# elasticNode.net
KiCad netlist of a schematic drawn in EAGLE
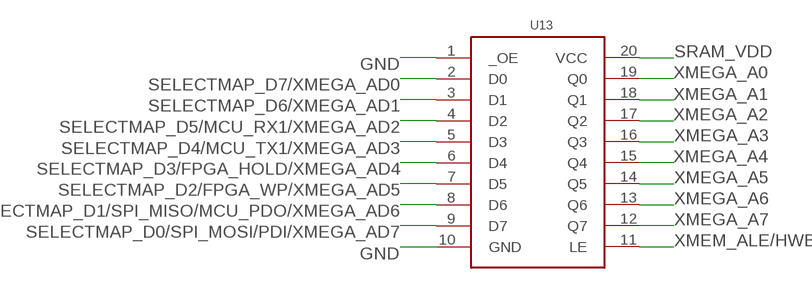
[diagram p0: schematic, sheet 1, part 1 of 2]
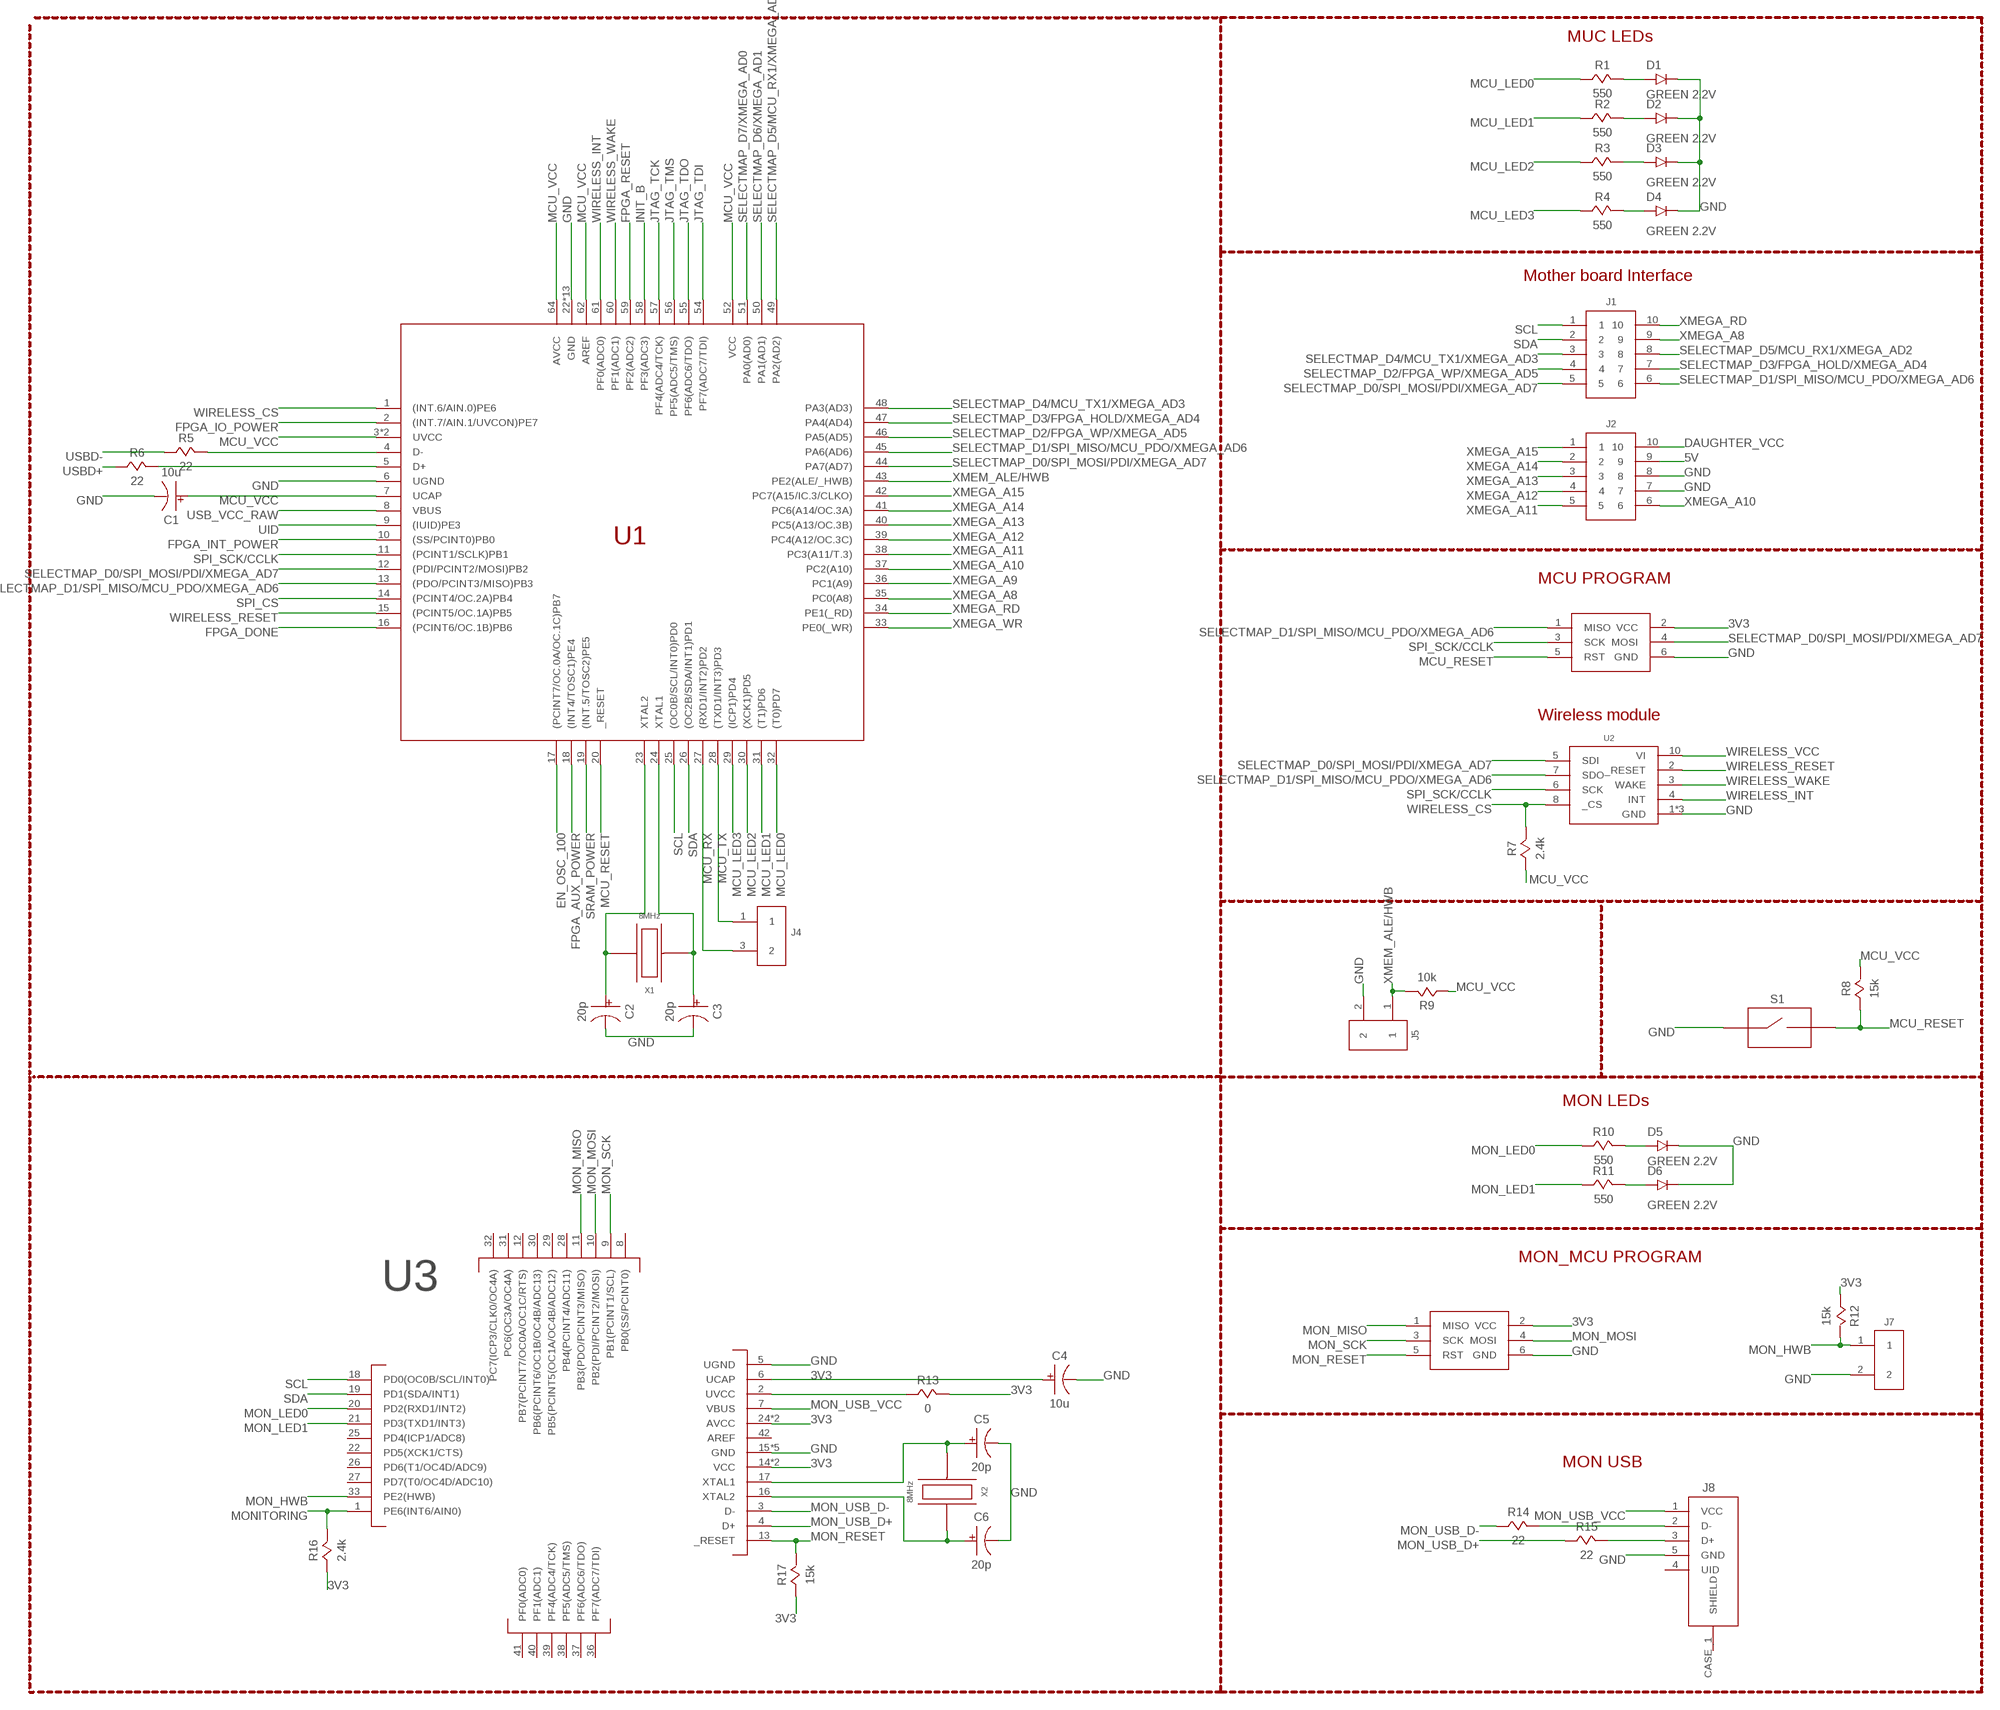
[diagram p1: schematic, sheet 1, part 2 of 2]
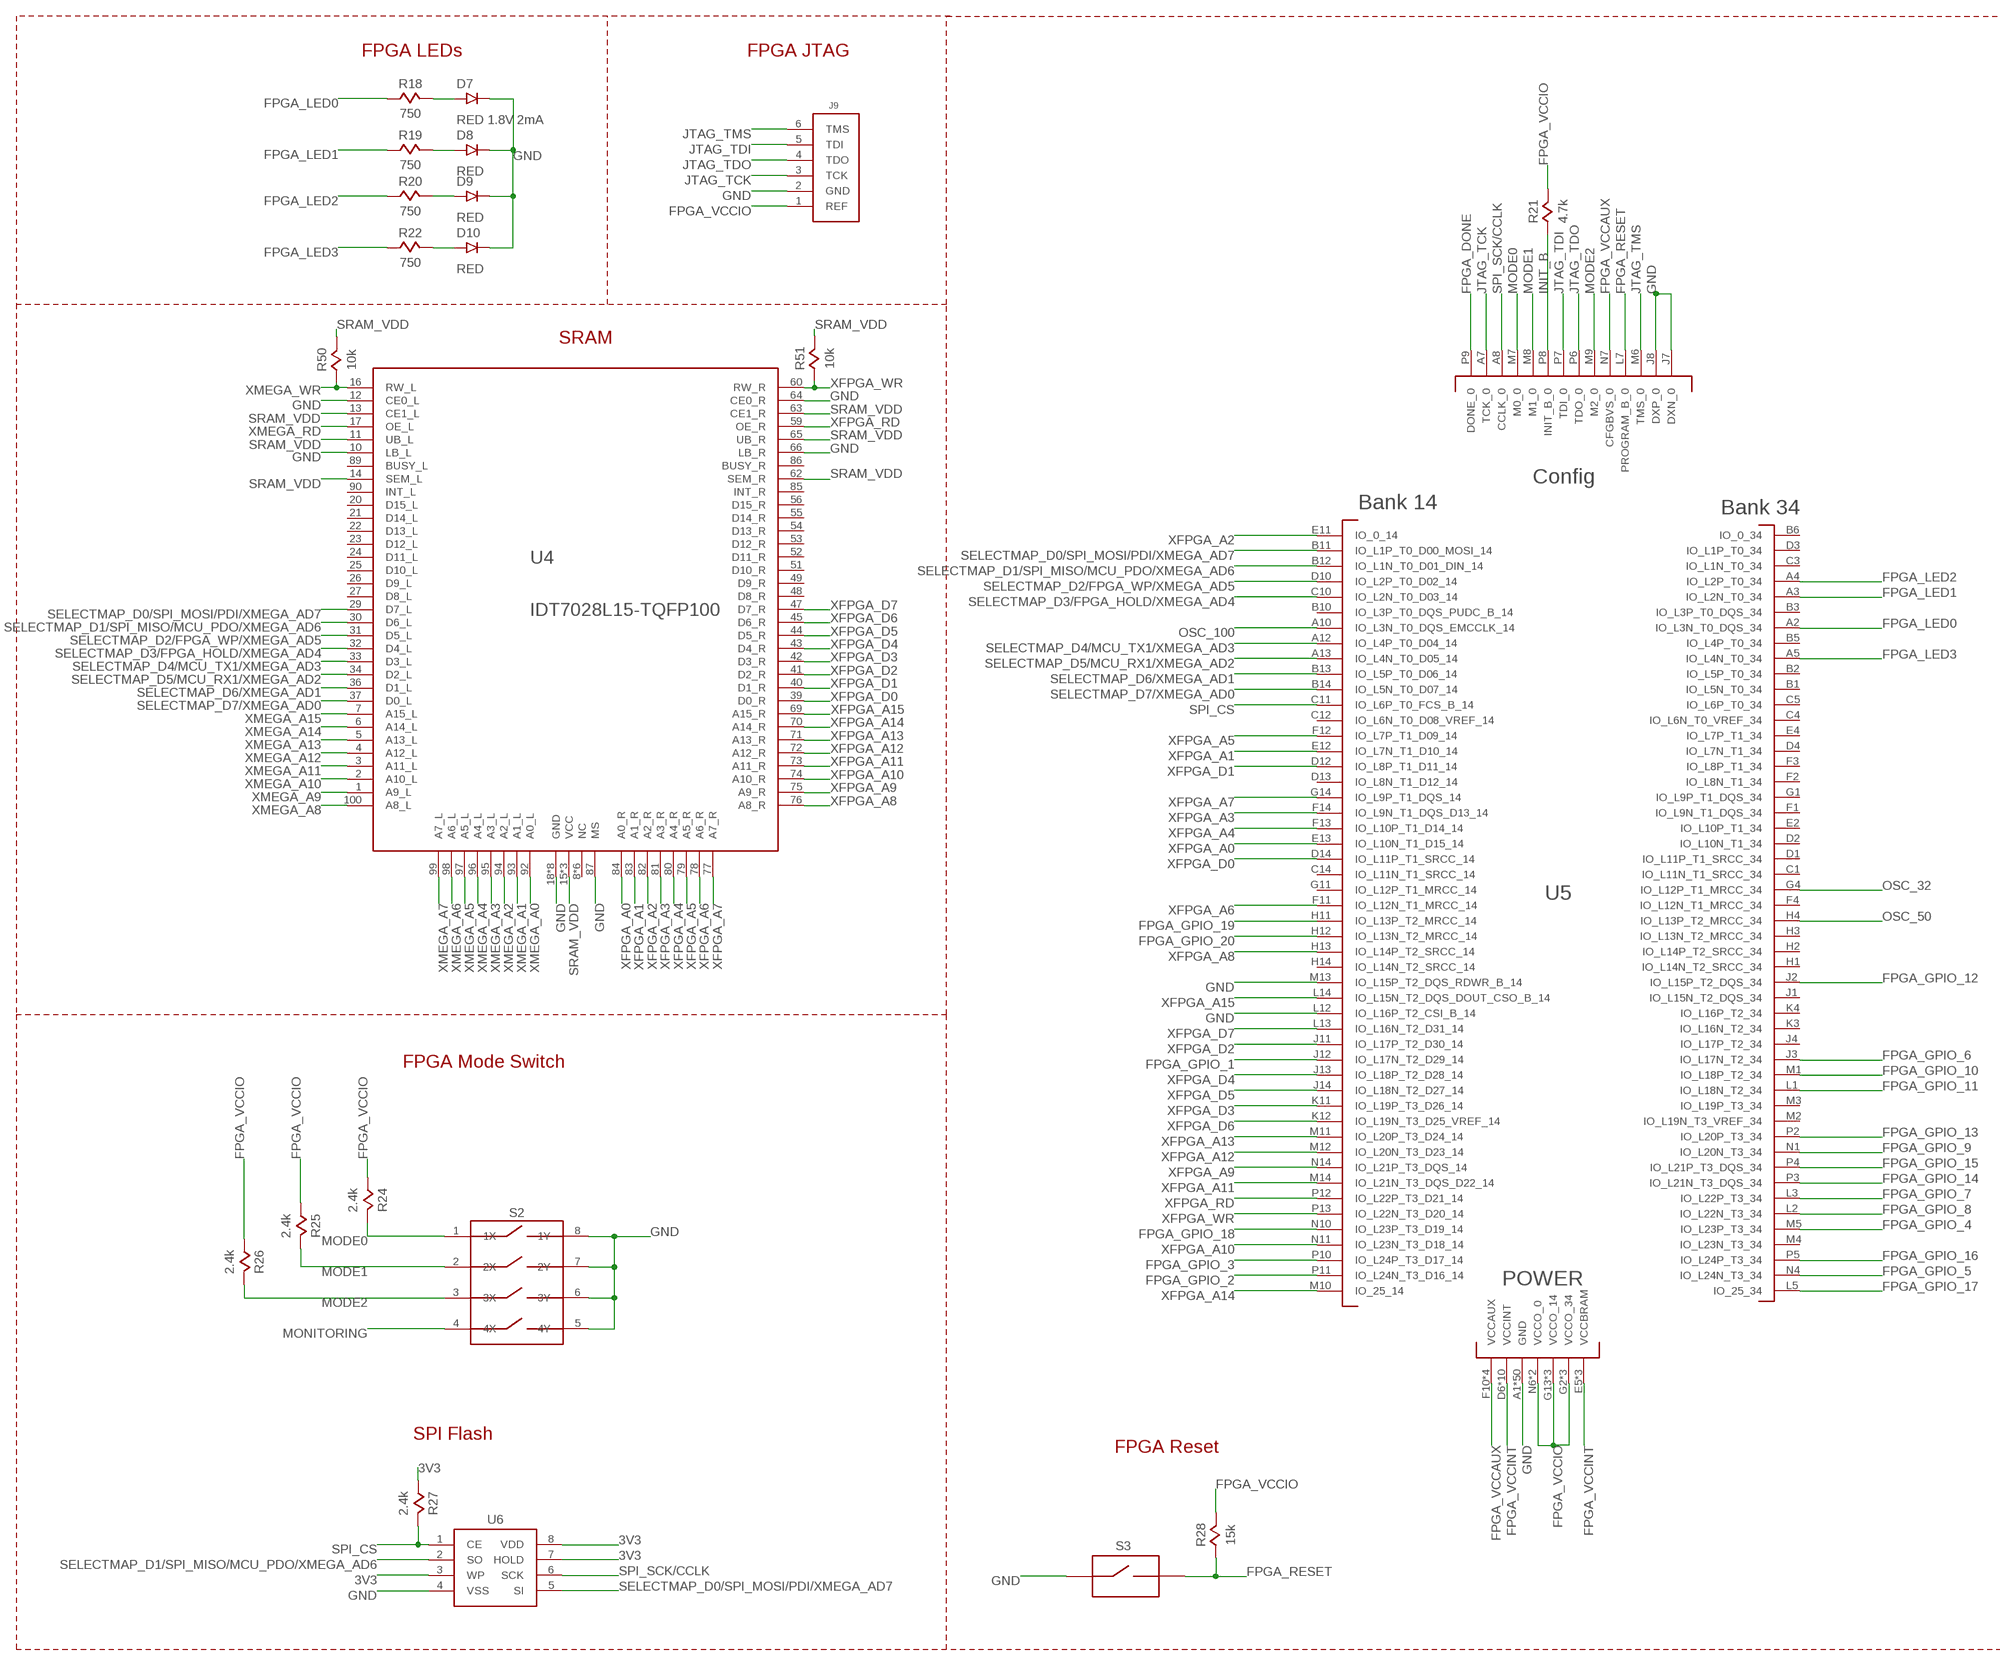
[diagram p2: schematic, sheet 2, part 1 of 2]
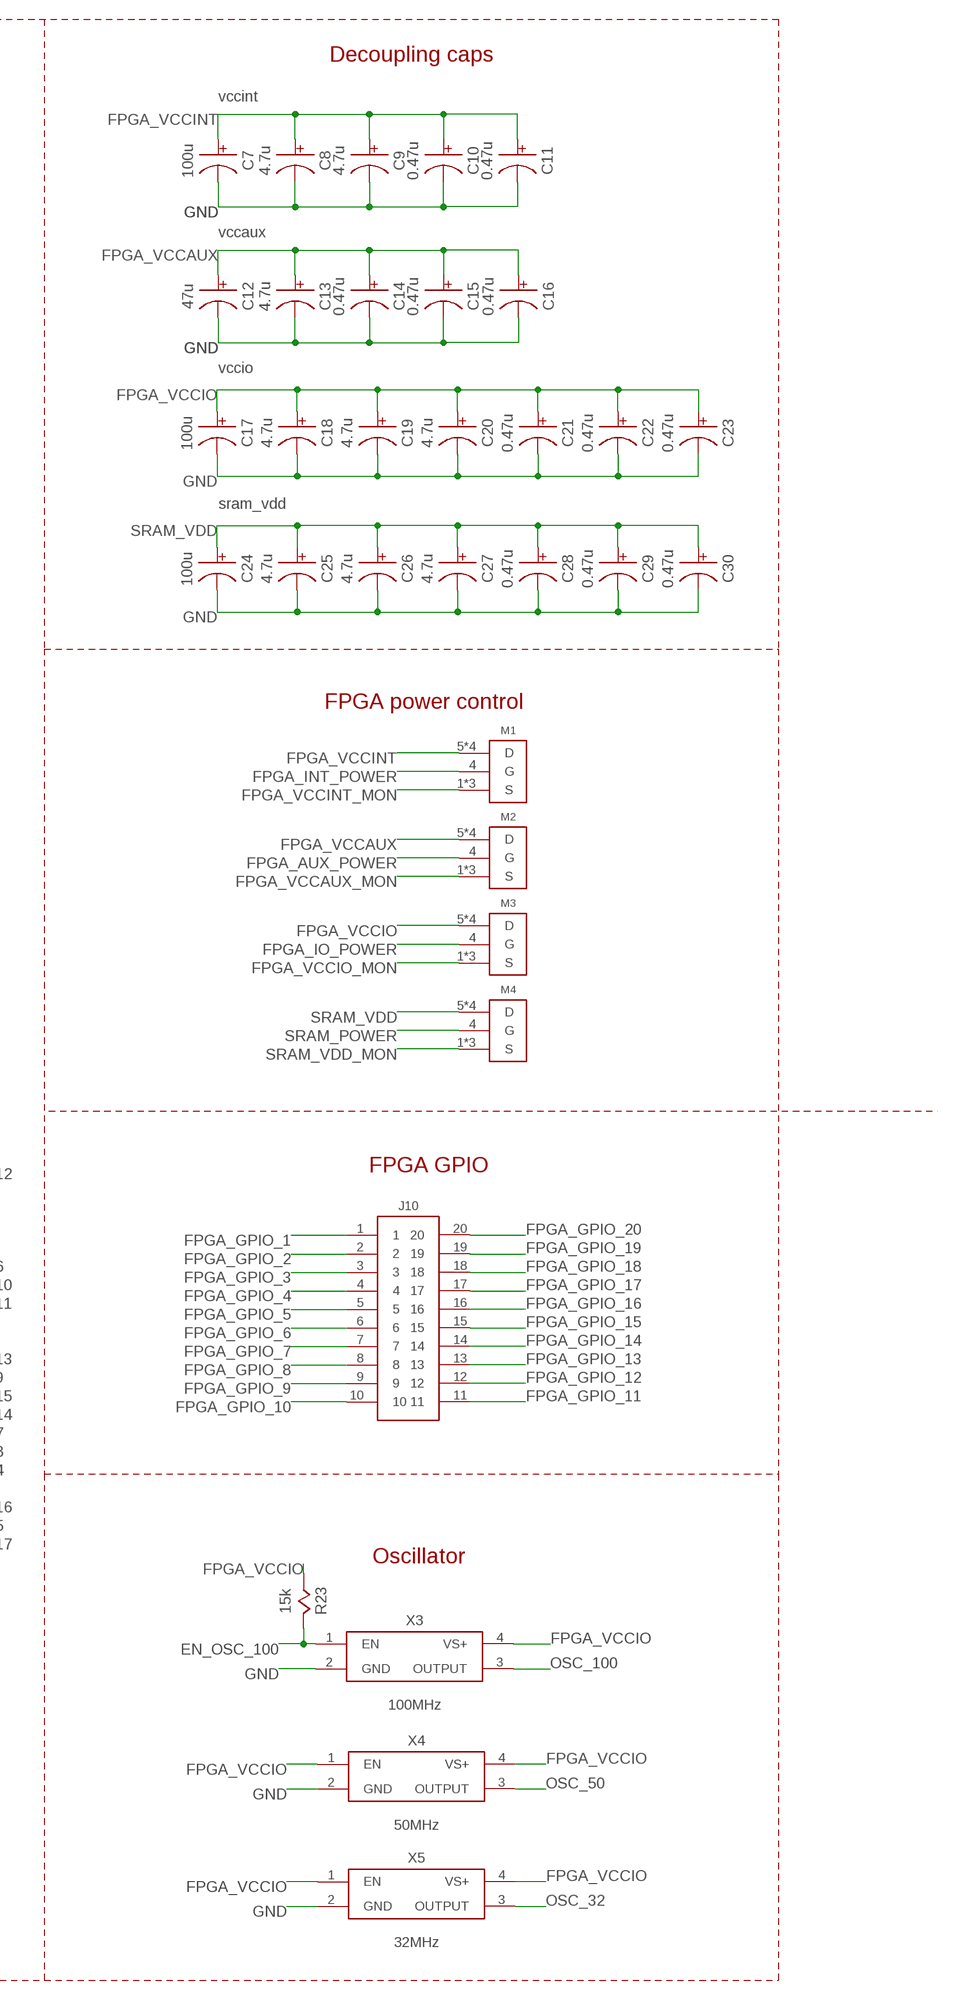
[diagram p3: schematic, sheet 2, part 2 of 2]
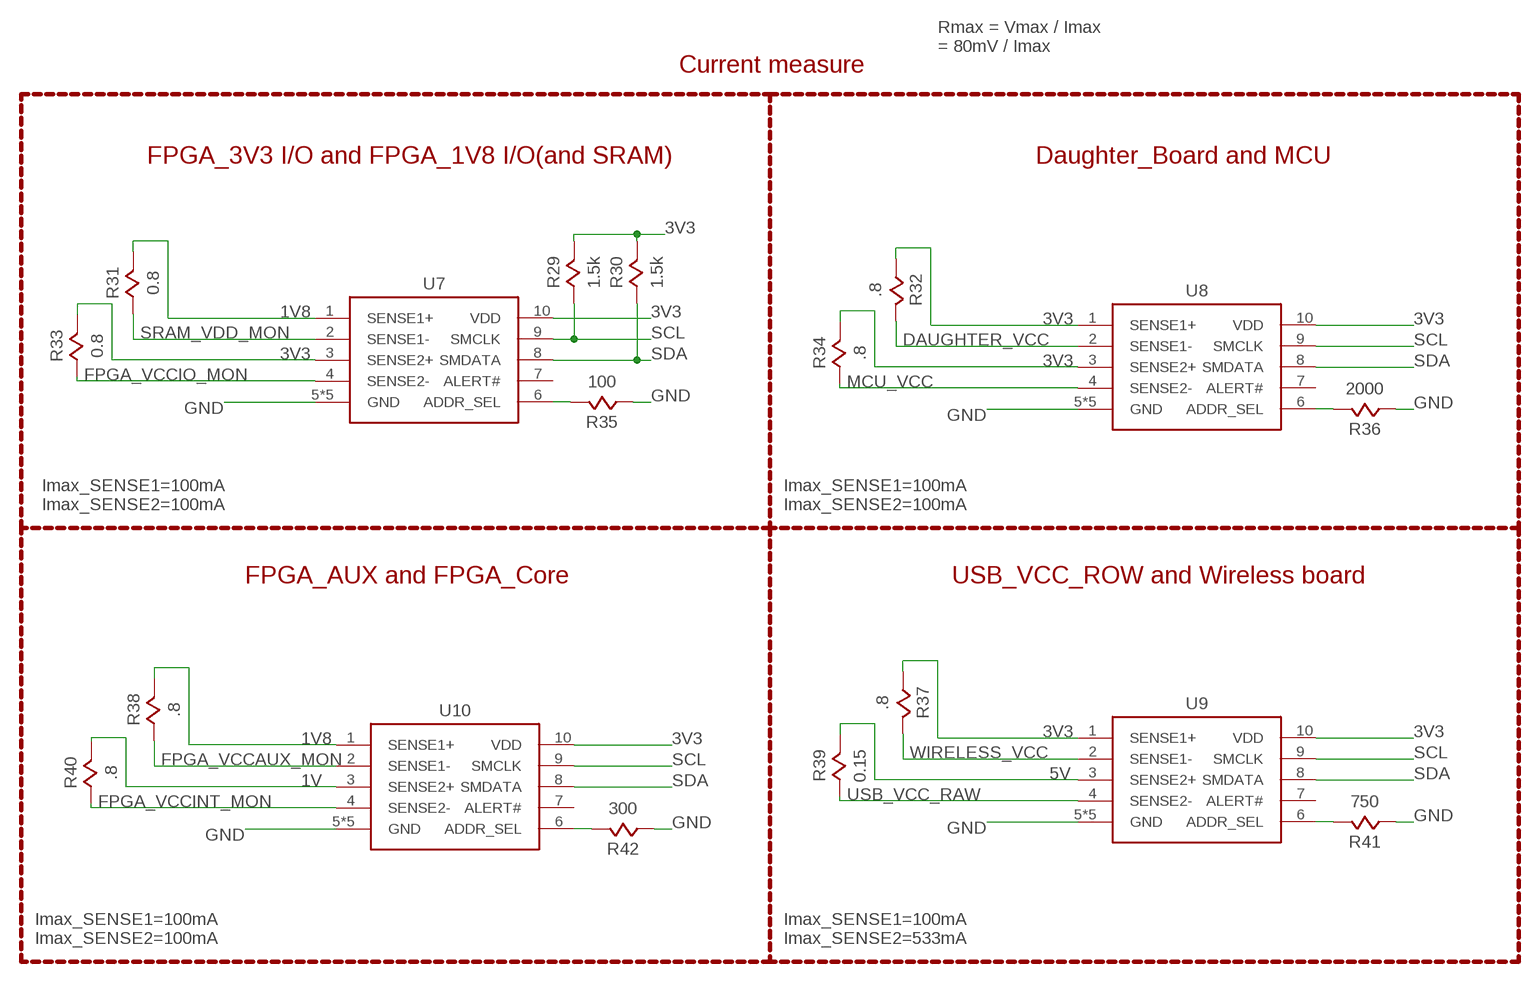
[diagram p4: schematic, sheet 3]
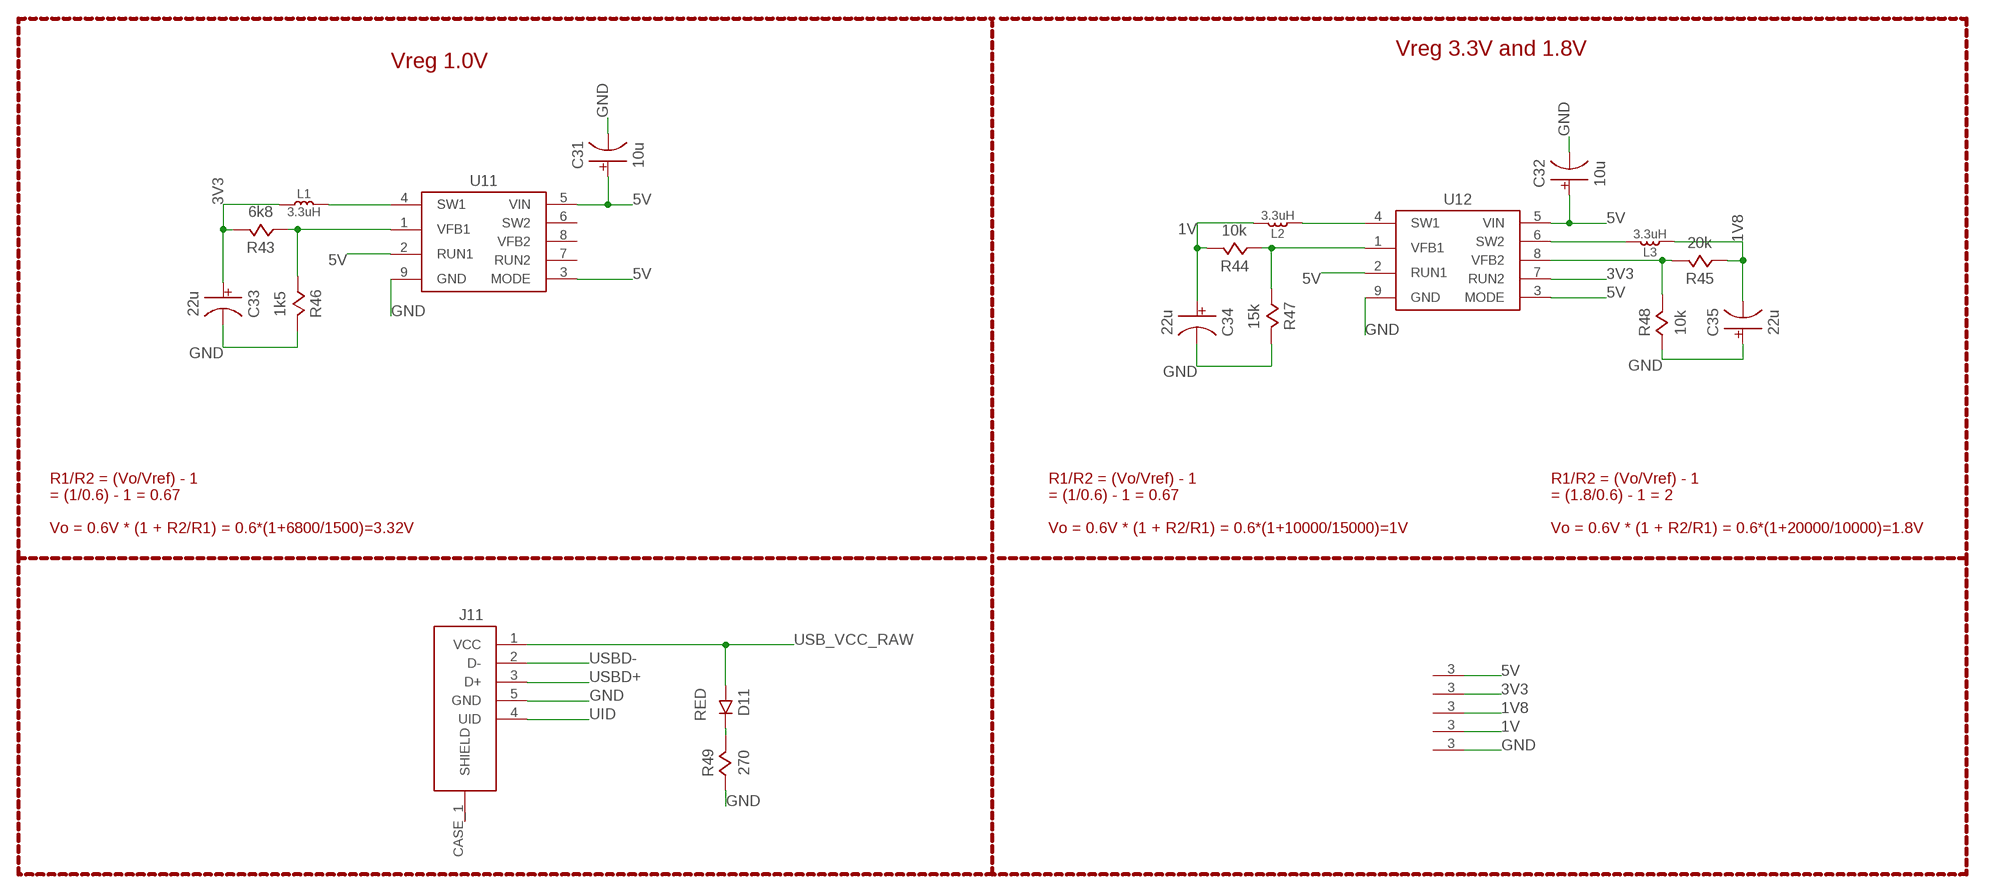
[diagram p5: schematic, sheet 4]

(export (version "E")
  (design (tool "Eeschema 10.0.6"))
  (components
    (comp (ref "C31")
      (value "10u")
      (footprint "eagle-import:0805")
      (libsource (lib "eagle-import") (part "CAPACITOR0805"))
    )
    (comp (ref "C32")
      (value "10u")
      (footprint "eagle-import:0805")
      (libsource (lib "eagle-import") (part "CAPACITOR0805"))
    )
    (comp (ref "C33")
      (value "22u")
      (footprint "eagle-import:0805")
      (libsource (lib "eagle-import") (part "CAPACITOR0805"))
    )
    (comp (ref "C34")
      (value "22u")
      (footprint "eagle-import:0805")
      (libsource (lib "eagle-import") (part "CAPACITOR0805"))
    )
    (comp (ref "C35")
      (value "22u")
      (footprint "eagle-import:0805")
      (libsource (lib "eagle-import") (part "CAPACITOR0805"))
    )
    (comp (ref "D11")
      (value "RED")
      (footprint "eagle-import:0805")
      (libsource (lib "eagle-import") (part "LED"))
    )
    (comp (ref "J11")
      (value "USB_CONNMICRO_SMT")
      (footprint "eagle-import:USB_MICRO_B_SMT")
      (libsource (lib "eagle-import") (part "USB_CONNMICRO_SMT"))
    )
    (comp (ref "L1")
      (value "3.3uH")
      (footprint "eagle-import:0805")
      (libsource (lib "eagle-import") (part "INDUCTOR"))
    )
    (comp (ref "L2")
      (value "3.3uH")
      (footprint "eagle-import:0805")
      (libsource (lib "eagle-import") (part "INDUCTOR"))
    )
    (comp (ref "L3")
      (value "3.3uH")
      (footprint "eagle-import:0805")
      (libsource (lib "eagle-import") (part "INDUCTOR"))
    )
    (comp (ref "R43")
      (value "6k8")
      (footprint "eagle-import:0805")
      (libsource (lib "eagle-import") (part "RESISTOR"))
    )
    (comp (ref "R44")
      (value "10k")
      (footprint "eagle-import:0805")
      (libsource (lib "eagle-import") (part "RESISTOR"))
    )
    (comp (ref "R45")
      (value "20k")
      (footprint "eagle-import:0805")
      (libsource (lib "eagle-import") (part "RESISTOR"))
    )
    (comp (ref "R46")
      (value "1k5")
      (footprint "eagle-import:0805")
      (libsource (lib "eagle-import") (part "RESISTOR"))
    )
    (comp (ref "R47")
      (value "15k")
      (footprint "eagle-import:0805")
      (libsource (lib "eagle-import") (part "RESISTOR"))
    )
    (comp (ref "R48")
      (value "10k")
      (footprint "eagle-import:0805")
      (libsource (lib "eagle-import") (part "RESISTOR"))
    )
    (comp (ref "R49")
      (value "270")
      (footprint "eagle-import:0805")
      (libsource (lib "eagle-import") (part "RESISTOR"))
    )
    (comp (ref "TP1")
      (value "TEST_POINTTHT")
      (footprint "eagle-import:THT")
      (libsource (lib "eagle-import") (part "TEST_POINTTHT"))
    )
    (comp (ref "TP2")
      (value "TEST_POINTTHT")
      (footprint "eagle-import:THT")
      (libsource (lib "eagle-import") (part "TEST_POINTTHT"))
    )
    (comp (ref "TP3")
      (value "TEST_POINTTHT")
      (footprint "eagle-import:THT")
      (libsource (lib "eagle-import") (part "TEST_POINTTHT"))
    )
    (comp (ref "TP4")
      (value "TEST_POINTTHT")
      (footprint "eagle-import:THT")
      (libsource (lib "eagle-import") (part "TEST_POINTTHT"))
    )
    (comp (ref "TP5")
      (value "TEST_POINTTHT")
      (footprint "eagle-import:THT")
      (libsource (lib "eagle-import") (part "TEST_POINTTHT"))
    )
    (comp (ref "U11")
      (value "LTC3419DFN")
      (footprint "eagle-import:DFN8")
      (libsource (lib "eagle-import") (part "LTC3419DFN"))
    )
    (comp (ref "U12")
      (value "LTC3419DFN")
      (footprint "eagle-import:DFN8")
      (libsource (lib "eagle-import") (part "LTC3419DFN"))
    )
    (comp (ref "C1")
      (value "10u")
      (footprint "eagle-import:0805")
      (libsource (lib "eagle-import") (part "CAPACITOR0805"))
    )
    (comp (ref "C2")
      (value "20p")
      (footprint "eagle-import:0805")
      (libsource (lib "eagle-import") (part "CAPACITOR0805"))
    )
    (comp (ref "C3")
      (value "20p")
      (footprint "eagle-import:0805")
      (libsource (lib "eagle-import") (part "CAPACITOR0805"))
    )
    (comp (ref "C4")
      (value "10u")
      (footprint "eagle-import:0805")
      (libsource (lib "eagle-import") (part "CAPACITOR0805"))
    )
    (comp (ref "C5")
      (value "20p")
      (footprint "eagle-import:0805")
      (libsource (lib "eagle-import") (part "CAPACITOR0805"))
    )
    (comp (ref "C6")
      (value "20p")
      (footprint "eagle-import:0805")
      (libsource (lib "eagle-import") (part "CAPACITOR0805"))
    )
    (comp (ref "D1")
      (value "GREEN 2.2V")
      (footprint "eagle-import:0805")
      (libsource (lib "eagle-import") (part "LED"))
    )
    (comp (ref "D2")
      (value "GREEN 2.2V")
      (footprint "eagle-import:0805")
      (libsource (lib "eagle-import") (part "LED"))
    )
    (comp (ref "D3")
      (value "GREEN 2.2V")
      (footprint "eagle-import:0805")
      (libsource (lib "eagle-import") (part "LED"))
    )
    (comp (ref "D4")
      (value "GREEN 2.2V")
      (footprint "eagle-import:0805")
      (libsource (lib "eagle-import") (part "LED"))
    )
    (comp (ref "D5")
      (value "GREEN 2.2V")
      (footprint "eagle-import:0805")
      (libsource (lib "eagle-import") (part "LED"))
    )
    (comp (ref "D6")
      (value "GREEN 2.2V")
      (footprint "eagle-import:0805")
      (libsource (lib "eagle-import") (part "LED"))
    )
    (comp (ref "J1")
      (value "FEMALE_HEADER_5X2")
      (footprint "eagle-import:5X2_HEADER_SMT_1.27")
      (libsource (lib "eagle-import") (part "FEMALE_HEADER_5X2"))
    )
    (comp (ref "J2")
      (value "FEMALE_HEADER_5X2")
      (footprint "eagle-import:5X2_HEADER_SMT_1.27")
      (libsource (lib "eagle-import") (part "FEMALE_HEADER_5X2"))
    )
    (comp (ref "J3")
      (value "ISP_CONN_6PIN")
      (footprint "eagle-import:ICSP_SMT")
      (fields (field (name "SPICEPREFIX") "X"))
      (libsource (lib "eagle-import") (part "ISP_CONN_6PIN"))
    )
    (comp (ref "J4")
      (value "FEMALE_HEADER_2X1")
      (footprint "eagle-import:2X1_HEADER")
      (libsource (lib "eagle-import") (part "FEMALE_HEADER_2X1"))
    )
    (comp (ref "J5")
      (value "JUMPER")
      (footprint "eagle-import:JUMPER_SMT")
      (libsource (lib "eagle-import") (part "JUMPER"))
    )
    (comp (ref "J6")
      (value "ISP_CONN_6PIN")
      (footprint "eagle-import:ICSP_SMT")
      (libsource (lib "eagle-import") (part "ISP_CONN_6PIN"))
    )
    (comp (ref "J7")
      (value "JUMPER")
      (footprint "eagle-import:JUMPER_SMT")
      (libsource (lib "eagle-import") (part "JUMPER"))
    )
    (comp (ref "J8")
      (value "USB_CONNMICRO_SMT")
      (footprint "eagle-import:USB_MICRO_B_SMT")
      (libsource (lib "eagle-import") (part "USB_CONNMICRO_SMT"))
    )
    (comp (ref "R1")
      (value "550")
      (footprint "eagle-import:0805")
      (libsource (lib "eagle-import") (part "RESISTOR"))
    )
    (comp (ref "R2")
      (value "550")
      (footprint "eagle-import:0805")
      (libsource (lib "eagle-import") (part "RESISTOR"))
    )
    (comp (ref "R3")
      (value "550")
      (footprint "eagle-import:0805")
      (libsource (lib "eagle-import") (part "RESISTOR"))
    )
    (comp (ref "R4")
      (value "550")
      (footprint "eagle-import:0805")
      (libsource (lib "eagle-import") (part "RESISTOR"))
    )
    (comp (ref "R5")
      (value "22")
      (footprint "eagle-import:0805")
      (libsource (lib "eagle-import") (part "RESISTOR"))
    )
    (comp (ref "R6")
      (value "22")
      (footprint "eagle-import:0805")
      (libsource (lib "eagle-import") (part "RESISTOR"))
    )
    (comp (ref "R7")
      (value "2.4k")
      (footprint "eagle-import:0805")
      (libsource (lib "eagle-import") (part "RESISTOR"))
    )
    (comp (ref "R8")
      (value "15k")
      (footprint "eagle-import:0805")
      (libsource (lib "eagle-import") (part "RESISTOR"))
    )
    (comp (ref "R9")
      (value "10k")
      (footprint "eagle-import:0805")
      (libsource (lib "eagle-import") (part "RESISTOR"))
    )
    (comp (ref "R10")
      (value "550")
      (footprint "eagle-import:0805")
      (libsource (lib "eagle-import") (part "RESISTOR"))
    )
    (comp (ref "R11")
      (value "550")
      (footprint "eagle-import:0805")
      (libsource (lib "eagle-import") (part "RESISTOR"))
    )
    (comp (ref "R12")
      (value "15k")
      (footprint "eagle-import:0805")
      (libsource (lib "eagle-import") (part "RESISTOR"))
    )
    (comp (ref "R13")
      (value "0")
      (footprint "eagle-import:0805")
      (libsource (lib "eagle-import") (part "RESISTOR"))
    )
    (comp (ref "R14")
      (value "22")
      (footprint "eagle-import:0805")
      (libsource (lib "eagle-import") (part "RESISTOR"))
    )
    (comp (ref "R15")
      (value "22")
      (footprint "eagle-import:0805")
      (libsource (lib "eagle-import") (part "RESISTOR"))
    )
    (comp (ref "R16")
      (value "2.4k")
      (footprint "eagle-import:0805")
      (libsource (lib "eagle-import") (part "RESISTOR"))
    )
    (comp (ref "R17")
      (value "15k")
      (footprint "eagle-import:0805")
      (libsource (lib "eagle-import") (part "RESISTOR"))
    )
    (comp (ref "S1")
      (value "SPST_BUTTON2PIN_SMT")
      (footprint "eagle-import:SPST_2PIN_SMT")
      (libsource (lib "eagle-import") (part "SPST_BUTTON2PIN_SMT"))
    )
    (comp (ref "U1")
      (value "AT90USB128")
      (footprint "eagle-import:QFN64")
      (libsource (lib "eagle-import") (part "AT90USB128"))
    )
    (comp (ref "U2")
      (value "MRF24J40MA")
      (footprint "eagle-import:MRF24J40MA")
      (libsource (lib "eagle-import") (part "MRF24J40MA"))
    )
    (comp (ref "U3")
      (value "ATMEGA32U4QFN")
      (footprint "eagle-import:QFN44")
      (libsource (lib "eagle-import") (part "ATMEGA32U4QFN"))
    )
    (comp (ref "U13")
      (value "74AHC573")
      (footprint "eagle-import:SOIC20")
      (libsource (lib "eagle-import") (part "74AHC573"))
    )
    (comp (ref "X1")
      (value "8MHz")
      (footprint "eagle-import:3.2X2.5_OSC")
      (libsource (lib "eagle-import") (part "QUARTZ"))
    )
    (comp (ref "X2")
      (value "8MHz")
      (footprint "eagle-import:3.2X2.5_OSC")
      (libsource (lib "eagle-import") (part "QUARTZ"))
    )
    (comp (ref "C7")
      (value "100u")
      (footprint "eagle-import:1210")
      (libsource (lib "eagle-import") (part "CAPACITOR1210"))
    )
    (comp (ref "C8")
      (value "4.7u")
      (footprint "eagle-import:0805")
      (libsource (lib "eagle-import") (part "CAPACITOR0805"))
    )
    (comp (ref "C9")
      (value "4.7u")
      (footprint "eagle-import:0805")
      (libsource (lib "eagle-import") (part "CAPACITOR0805"))
    )
    (comp (ref "C10")
      (value "0.47u")
      (footprint "eagle-import:0805")
      (libsource (lib "eagle-import") (part "CAPACITOR0805"))
    )
    (comp (ref "C11")
      (value "0.47u")
      (footprint "eagle-import:0805")
      (libsource (lib "eagle-import") (part "CAPACITOR0805"))
    )
    (comp (ref "C12")
      (value "47u")
      (footprint "eagle-import:1210")
      (libsource (lib "eagle-import") (part "CAPACITOR1210"))
    )
    (comp (ref "C13")
      (value "4.7u")
      (footprint "eagle-import:0805")
      (libsource (lib "eagle-import") (part "CAPACITOR0805"))
    )
    (comp (ref "C14")
      (value "0.47u")
      (footprint "eagle-import:0805")
      (libsource (lib "eagle-import") (part "CAPACITOR0805"))
    )
    (comp (ref "C15")
      (value "0.47u")
      (footprint "eagle-import:0805")
      (libsource (lib "eagle-import") (part "CAPACITOR0805"))
    )
    (comp (ref "C16")
      (value "0.47u")
      (footprint "eagle-import:0805")
      (libsource (lib "eagle-import") (part "CAPACITOR0805"))
    )
    (comp (ref "C17")
      (value "100u")
      (footprint "eagle-import:1210")
      (libsource (lib "eagle-import") (part "CAPACITOR1210"))
    )
    (comp (ref "C18")
      (value "4.7u")
      (footprint "eagle-import:0805")
      (libsource (lib "eagle-import") (part "CAPACITOR0805"))
    )
    (comp (ref "C19")
      (value "4.7u")
      (footprint "eagle-import:0805")
      (libsource (lib "eagle-import") (part "CAPACITOR0805"))
    )
    (comp (ref "C20")
      (value "4.7u")
      (footprint "eagle-import:0805")
      (libsource (lib "eagle-import") (part "CAPACITOR0805"))
    )
    (comp (ref "C21")
      (value "0.47u")
      (footprint "eagle-import:0805")
      (libsource (lib "eagle-import") (part "CAPACITOR0805"))
    )
    (comp (ref "C22")
      (value "0.47u")
      (footprint "eagle-import:0805")
      (libsource (lib "eagle-import") (part "CAPACITOR0805"))
    )
    (comp (ref "C23")
      (value "0.47u")
      (footprint "eagle-import:0805")
      (libsource (lib "eagle-import") (part "CAPACITOR0805"))
    )
    (comp (ref "C24")
      (value "100u")
      (footprint "eagle-import:1210")
      (libsource (lib "eagle-import") (part "CAPACITOR1210"))
    )
    (comp (ref "C25")
      (value "4.7u")
      (footprint "eagle-import:0805")
      (libsource (lib "eagle-import") (part "CAPACITOR0805"))
    )
    (comp (ref "C26")
      (value "4.7u")
      (footprint "eagle-import:0805")
      (libsource (lib "eagle-import") (part "CAPACITOR0805"))
    )
    (comp (ref "C27")
      (value "4.7u")
      (footprint "eagle-import:0805")
      (libsource (lib "eagle-import") (part "CAPACITOR0805"))
    )
    (comp (ref "C28")
      (value "0.47u")
      (footprint "eagle-import:0805")
      (libsource (lib "eagle-import") (part "CAPACITOR0805"))
    )
    (comp (ref "C29")
      (value "0.47u")
      (footprint "eagle-import:0805")
      (libsource (lib "eagle-import") (part "CAPACITOR0805"))
    )
    (comp (ref "C30")
      (value "0.47u")
      (footprint "eagle-import:0805")
      (libsource (lib "eagle-import") (part "CAPACITOR0805"))
    )
    (comp (ref "D7")
      (value "RED 1.8V 2mA")
      (footprint "eagle-import:0805")
      (libsource (lib "eagle-import") (part "LED"))
    )
    (comp (ref "D8")
      (value "RED")
      (footprint "eagle-import:0805")
      (libsource (lib "eagle-import") (part "LED"))
    )
    (comp (ref "D9")
      (value "RED")
      (footprint "eagle-import:0805")
      (libsource (lib "eagle-import") (part "LED"))
    )
    (comp (ref "D10")
      (value "RED")
      (footprint "eagle-import:0805")
      (libsource (lib "eagle-import") (part "LED"))
    )
    (comp (ref "J9")
      (value "JTAG_CONN_6PINSMT")
      (footprint "eagle-import:6X1_JTAG")
      (libsource (lib "eagle-import") (part "JTAG_CONN_6PINSMT"))
    )
    (comp (ref "J10")
      (value "FEMALE_HEADER_10X2")
      (footprint "eagle-import:10X2_HEADER_SMT")
      (libsource (lib "eagle-import") (part "FEMALE_HEADER_10X2"))
    )
    (comp (ref "M1")
      (value "SISS23DN")
      (footprint "eagle-import:POWERPAK1212-8")
      (libsource (lib "eagle-import") (part "SISS23DN"))
    )
    (comp (ref "M2")
      (value "SISS23DN")
      (footprint "eagle-import:POWERPAK1212-8")
      (libsource (lib "eagle-import") (part "SISS23DN"))
    )
    (comp (ref "M3")
      (value "SISS23DN")
      (footprint "eagle-import:POWERPAK1212-8")
      (libsource (lib "eagle-import") (part "SISS23DN"))
    )
    (comp (ref "M4")
      (value "SISS23DN")
      (footprint "eagle-import:POWERPAK1212-8")
      (libsource (lib "eagle-import") (part "SISS23DN"))
    )
    (comp (ref "R18")
      (value "750")
      (footprint "eagle-import:0805")
      (libsource (lib "eagle-import") (part "RESISTOR"))
    )
    (comp (ref "R19")
      (value "750")
      (footprint "eagle-import:0805")
      (libsource (lib "eagle-import") (part "RESISTOR"))
    )
    (comp (ref "R20")
      (value "750")
      (footprint "eagle-import:0805")
      (libsource (lib "eagle-import") (part "RESISTOR"))
    )
    (comp (ref "R21")
      (value "4.7k")
      (footprint "eagle-import:0805")
      (libsource (lib "eagle-import") (part "RESISTOR"))
    )
    (comp (ref "R22")
      (value "750")
      (footprint "eagle-import:0805")
      (libsource (lib "eagle-import") (part "RESISTOR"))
    )
    (comp (ref "R23")
      (value "15k")
      (footprint "eagle-import:0805")
      (libsource (lib "eagle-import") (part "RESISTOR"))
    )
    (comp (ref "R24")
      (value "2.4k")
      (footprint "eagle-import:0805")
      (libsource (lib "eagle-import") (part "RESISTOR"))
    )
    (comp (ref "R25")
      (value "2.4k")
      (footprint "eagle-import:0805")
      (libsource (lib "eagle-import") (part "RESISTOR"))
    )
    (comp (ref "R26")
      (value "2.4k")
      (footprint "eagle-import:0805")
      (libsource (lib "eagle-import") (part "RESISTOR"))
    )
    (comp (ref "R27")
      (value "2.4k")
      (footprint "eagle-import:0805")
      (libsource (lib "eagle-import") (part "RESISTOR"))
    )
    (comp (ref "R28")
      (value "15k")
      (footprint "eagle-import:0805")
      (libsource (lib "eagle-import") (part "RESISTOR"))
    )
    (comp (ref "R50")
      (value "10k")
      (footprint "eagle-import:0805")
      (libsource (lib "eagle-import") (part "RESISTOR"))
    )
    (comp (ref "R51")
      (value "10k")
      (footprint "eagle-import:0805")
      (libsource (lib "eagle-import") (part "RESISTOR"))
    )
    (comp (ref "S2")
      (value "SPST_DIP_4")
      (footprint "eagle-import:SPST_DIP4_SMT")
      (libsource (lib "eagle-import") (part "SPST_DIP_4"))
    )
    (comp (ref "S3")
      (value "SPST_BUTTON2PIN_SMT")
      (footprint "eagle-import:SPST_2PIN_SMT")
      (libsource (lib "eagle-import") (part "SPST_BUTTON2PIN_SMT"))
    )
    (comp (ref "U4")
      (value "IDT7028L15-TQFP100")
      (footprint "eagle-import:TQFP100")
      (libsource (lib "eagle-import") (part "IDT7028L15-TQFP100"))
    )
    (comp (ref "U5")
      (value "SPARTAN7-LX15")
      (footprint "eagle-import:FTGB196")
      (libsource (lib "eagle-import") (part "SPARTAN7-LX15"))
    )
    (comp (ref "U6")
      (value "SST26VF032BWDFN")
      (footprint "eagle-import:WDFN8")
      (libsource (lib "eagle-import") (part "SST26VF032BWDFN"))
    )
    (comp (ref "X3")
      (value "100MHz")
      (footprint "eagle-import:3.2X2.5_OSC")
      (libsource (lib "eagle-import") (part "OSCILLATOR3.2X2.5"))
    )
    (comp (ref "X4")
      (value "50MHz")
      (footprint "eagle-import:3.2X2.5_OSC")
      (libsource (lib "eagle-import") (part "OSCILLATOR3.2X2.5"))
    )
    (comp (ref "X5")
      (value "32MHz")
      (footprint "eagle-import:3.2X2.5_OSC")
      (libsource (lib "eagle-import") (part "OSCILLATOR3.2X2.5"))
    )
    (comp (ref "R29")
      (value "1.5k")
      (footprint "eagle-import:0805")
      (libsource (lib "eagle-import") (part "RESISTOR"))
    )
    (comp (ref "R30")
      (value "1.5k")
      (footprint "eagle-import:0805")
      (libsource (lib "eagle-import") (part "RESISTOR"))
    )
    (comp (ref "R31")
      (value "0.8")
      (footprint "eagle-import:0805")
      (libsource (lib "eagle-import") (part "RESISTOR"))
    )
    (comp (ref "R32")
      (value ".8")
      (footprint "eagle-import:0805")
      (libsource (lib "eagle-import") (part "RESISTOR"))
    )
    (comp (ref "R33")
      (value "0.8")
      (footprint "eagle-import:0805")
      (libsource (lib "eagle-import") (part "RESISTOR"))
    )
    (comp (ref "R34")
      (value ".8")
      (footprint "eagle-import:0805")
      (libsource (lib "eagle-import") (part "RESISTOR"))
    )
    (comp (ref "R35")
      (value "100")
      (footprint "eagle-import:0805")
      (libsource (lib "eagle-import") (part "RESISTOR"))
    )
    (comp (ref "R36")
      (value "2000")
      (footprint "eagle-import:0805")
      (libsource (lib "eagle-import") (part "RESISTOR"))
    )
    (comp (ref "R37")
      (value ".8")
      (footprint "eagle-import:0805")
      (libsource (lib "eagle-import") (part "RESISTOR"))
    )
    (comp (ref "R38")
      (value ".8")
      (footprint "eagle-import:0805")
      (libsource (lib "eagle-import") (part "RESISTOR"))
    )
    (comp (ref "R39")
      (value "0.15")
      (footprint "eagle-import:0805")
      (libsource (lib "eagle-import") (part "RESISTOR"))
    )
    (comp (ref "R40")
      (value ".8")
      (footprint "eagle-import:0805")
      (libsource (lib "eagle-import") (part "RESISTOR"))
    )
    (comp (ref "R41")
      (value "750")
      (footprint "eagle-import:0805")
      (libsource (lib "eagle-import") (part "RESISTOR"))
    )
    (comp (ref "R42")
      (value "300")
      (footprint "eagle-import:0805")
      (libsource (lib "eagle-import") (part "RESISTOR"))
    )
    (comp (ref "U7")
      (value "PAC1720")
      (footprint "eagle-import:VDFN10")
      (libsource (lib "eagle-import") (part "PAC1720"))
    )
    (comp (ref "U8")
      (value "PAC1720")
      (footprint "eagle-import:VDFN10")
      (libsource (lib "eagle-import") (part "PAC1720"))
    )
    (comp (ref "U9")
      (value "PAC1720")
      (footprint "eagle-import:VDFN10")
      (libsource (lib "eagle-import") (part "PAC1720"))
    )
    (comp (ref "U10")
      (value "PAC1720")
      (footprint "eagle-import:VDFN10")
      (libsource (lib "eagle-import") (part "PAC1720"))
    )
  )
  (nets
    (net (code "1") (name "1V") (class "Default")
      (node (ref "C34") (pin "1") (pinfunction "P$1_1") (pintype "bidirectional"))
      (node (ref "L2") (pin "2") (pinfunction "P$2_2") (pintype "bidirectional"))
      (node (ref "R40") (pin "2") (pinfunction "2_2") (pintype "bidirectional"))
      (node (ref "R44") (pin "2") (pinfunction "2_2") (pintype "bidirectional"))
      (node (ref "TP4") (pin "3") (pinfunction ">NAME_3") (pintype "bidirectional"))
      (node (ref "U10") (pin "3") (pinfunction "SENSE2+_3") (pintype "bidirectional"))
    )
    (net (code "2") (name "1V8") (class "Default")
      (node (ref "C35") (pin "2") (pinfunction "P$2_2") (pintype "bidirectional"))
      (node (ref "L3") (pin "1") (pinfunction "P$1_1") (pintype "bidirectional"))
      (node (ref "R31") (pin "2") (pinfunction "2_2") (pintype "bidirectional"))
      (node (ref "R38") (pin "2") (pinfunction "2_2") (pintype "bidirectional"))
      (node (ref "R45") (pin "1") (pinfunction "1_1") (pintype "bidirectional"))
      (node (ref "TP3") (pin "3") (pinfunction ">NAME_3") (pintype "bidirectional"))
      (node (ref "U10") (pin "1") (pinfunction "SENSE1+_1") (pintype "bidirectional"))
      (node (ref "U7") (pin "1") (pinfunction "SENSE1+_1") (pintype "bidirectional"))
    )
    (net (code "3") (name "3V3") (class "Default")
      (node (ref "C33") (pin "1") (pinfunction "P$1_1") (pintype "bidirectional"))
      (node (ref "C4") (pin "1") (pinfunction "P$1_1") (pintype "bidirectional"))
      (node (ref "J3") (pin "2") (pinfunction "VCC_2") (pintype "bidirectional"))
      (node (ref "J6") (pin "2") (pinfunction "VCC_2") (pintype "bidirectional"))
      (node (ref "L1") (pin "1") (pinfunction "P$1_1") (pintype "bidirectional"))
      (node (ref "R12") (pin "1") (pinfunction "1_1") (pintype "bidirectional"))
      (node (ref "R13") (pin "2") (pinfunction "2_2") (pintype "bidirectional"))
      (node (ref "R16") (pin "1") (pinfunction "1_1") (pintype "bidirectional"))
      (node (ref "R17") (pin "1") (pinfunction "1_1") (pintype "bidirectional"))
      (node (ref "R27") (pin "1") (pinfunction "1_1") (pintype "bidirectional"))
      (node (ref "R29") (pin "2") (pinfunction "2_2") (pintype "bidirectional"))
      (node (ref "R30") (pin "2") (pinfunction "2_2") (pintype "bidirectional"))
      (node (ref "R32") (pin "2") (pinfunction "2_2") (pintype "bidirectional"))
      (node (ref "R33") (pin "2") (pinfunction "2_2") (pintype "bidirectional"))
      (node (ref "R34") (pin "2") (pinfunction "2_2") (pintype "bidirectional"))
      (node (ref "R37") (pin "2") (pinfunction "2_2") (pintype "bidirectional"))
      (node (ref "R43") (pin "2") (pinfunction "2_2") (pintype "bidirectional"))
      (node (ref "TP2") (pin "3") (pinfunction ">NAME_3") (pintype "bidirectional"))
      (node (ref "U10") (pin "10") (pinfunction "VDD_10") (pintype "bidirectional"))
      (node (ref "U12") (pin "7") (pinfunction "RUN2_7") (pintype "bidirectional"))
      (node (ref "U3") (pin "14") (pinfunction "VCC_14") (pintype "bidirectional"))
      (node (ref "U3") (pin "24") (pinfunction "AVCC_24") (pintype "bidirectional"))
      (node (ref "U3") (pin "34") (pinfunction "VCC_34") (pintype "bidirectional"))
      (node (ref "U3") (pin "44") (pinfunction "AVCC_44") (pintype "bidirectional"))
      (node (ref "U3") (pin "6") (pinfunction "UCAP_6") (pintype "bidirectional"))
      (node (ref "U6") (pin "3") (pinfunction "WP_3") (pintype "bidirectional"))
      (node (ref "U6") (pin "7") (pinfunction "HOLD_7") (pintype "bidirectional"))
      (node (ref "U6") (pin "8") (pinfunction "VDD_8") (pintype "bidirectional"))
      (node (ref "U7") (pin "10") (pinfunction "VDD_10") (pintype "bidirectional"))
      (node (ref "U7") (pin "3") (pinfunction "SENSE2+_3") (pintype "bidirectional"))
      (node (ref "U8") (pin "1") (pinfunction "SENSE1+_1") (pintype "bidirectional"))
      (node (ref "U8") (pin "10") (pinfunction "VDD_10") (pintype "bidirectional"))
      (node (ref "U8") (pin "3") (pinfunction "SENSE2+_3") (pintype "bidirectional"))
      (node (ref "U9") (pin "1") (pinfunction "SENSE1+_1") (pintype "bidirectional"))
      (node (ref "U9") (pin "10") (pinfunction "VDD_10") (pintype "bidirectional"))
    )
    (net (code "4") (name "5V") (class "Default")
      (node (ref "C31") (pin "1") (pinfunction "P$1_1") (pintype "bidirectional"))
      (node (ref "C32") (pin "1") (pinfunction "P$1_1") (pintype "bidirectional"))
      (node (ref "J2") (pin "9") (pinfunction "9_9") (pintype "bidirectional"))
      (node (ref "R39") (pin "2") (pinfunction "2_2") (pintype "bidirectional"))
      (node (ref "TP1") (pin "3") (pinfunction ">NAME_3") (pintype "bidirectional"))
      (node (ref "U11") (pin "2") (pinfunction "RUN1_2") (pintype "bidirectional"))
      (node (ref "U11") (pin "3") (pinfunction "MODE_3") (pintype "bidirectional"))
      (node (ref "U11") (pin "5") (pinfunction "VIN_5") (pintype "bidirectional"))
      (node (ref "U12") (pin "2") (pinfunction "RUN1_2") (pintype "bidirectional"))
      (node (ref "U12") (pin "3") (pinfunction "MODE_3") (pintype "bidirectional"))
      (node (ref "U12") (pin "5") (pinfunction "VIN_5") (pintype "bidirectional"))
      (node (ref "U9") (pin "3") (pinfunction "SENSE2+_3") (pintype "bidirectional"))
    )
    (net (code "5") (name "DAUGHTER_VCC") (class "Default")
      (node (ref "J2") (pin "10") (pinfunction "10_10") (pintype "bidirectional"))
      (node (ref "R32") (pin "1") (pinfunction "1_1") (pintype "bidirectional"))
      (node (ref "U8") (pin "2") (pinfunction "SENSE1-_2") (pintype "bidirectional"))
    )
    (net (code "6") (name "EN_OSC_100") (class "Default")
      (node (ref "R23") (pin "1") (pinfunction "1_1") (pintype "bidirectional"))
      (node (ref "U1") (pin "17") (pinfunction "(PCINT7/OC.0A/OC.1C)PB7_17") (pintype "bidirectional"))
      (node (ref "X3") (pin "1") (pinfunction "EN_1") (pintype "bidirectional"))
    )
    (net (code "7") (name "FPGA_AUX_POWER") (class "Default")
      (node (ref "M2") (pin "4") (pinfunction "G_4") (pintype "bidirectional"))
      (node (ref "U1") (pin "18") (pinfunction "(INT4/TOSC1)PE4_18") (pintype "bidirectional"))
    )
    (net (code "8") (name "FPGA_DONE") (class "Default")
      (node (ref "U1") (pin "16") (pinfunction "(PCINT6/OC.1B)PB6_16") (pintype "bidirectional"))
      (node (ref "U5") (pin "P9") (pinfunction "DONE_0_P9") (pintype "bidirectional"))
    )
    (net (code "9") (name "FPGA_GPIO_1") (class "Default")
      (node (ref "J10") (pin "1") (pinfunction "1_1") (pintype "bidirectional"))
      (node (ref "U5") (pin "J12") (pinfunction "IO_L17N_T2_D29_14_J12") (pintype "bidirectional"))
    )
    (net (code "10") (name "FPGA_GPIO_2") (class "Default")
      (node (ref "J10") (pin "2") (pinfunction "2_2") (pintype "bidirectional"))
      (node (ref "U5") (pin "P11") (pinfunction "IO_L24N_T3_D16_14_P11") (pintype "bidirectional"))
    )
    (net (code "11") (name "FPGA_GPIO_3") (class "Default")
      (node (ref "J10") (pin "3") (pinfunction "3_3") (pintype "bidirectional"))
      (node (ref "U5") (pin "P10") (pinfunction "IO_L24P_T3_D17_14_P10") (pintype "bidirectional"))
    )
    (net (code "12") (name "FPGA_GPIO_4") (class "Default")
      (node (ref "J10") (pin "4") (pinfunction "4_4") (pintype "bidirectional"))
      (node (ref "U5") (pin "M5") (pinfunction "IO_L23P_T3_34_M5") (pintype "bidirectional"))
    )
    (net (code "13") (name "FPGA_GPIO_5") (class "Default")
      (node (ref "J10") (pin "5") (pinfunction "5_5") (pintype "bidirectional"))
      (node (ref "U5") (pin "N4") (pinfunction "IO_L24N_T3_34_N4") (pintype "bidirectional"))
    )
    (net (code "14") (name "FPGA_GPIO_6") (class "Default")
      (node (ref "J10") (pin "6") (pinfunction "6_6") (pintype "bidirectional"))
      (node (ref "U5") (pin "J3") (pinfunction "IO_L17N_T2_34_J3") (pintype "bidirectional"))
    )
    (net (code "15") (name "FPGA_GPIO_7") (class "Default")
      (node (ref "J10") (pin "7") (pinfunction "7_7") (pintype "bidirectional"))
      (node (ref "U5") (pin "L3") (pinfunction "IO_L22P_T3_34_L3") (pintype "bidirectional"))
    )
    (net (code "16") (name "FPGA_GPIO_8") (class "Default")
      (node (ref "J10") (pin "8") (pinfunction "8_8") (pintype "bidirectional"))
      (node (ref "U5") (pin "L2") (pinfunction "IO_L22N_T3_34_L2") (pintype "bidirectional"))
    )
    (net (code "17") (name "FPGA_GPIO_9") (class "Default")
      (node (ref "J10") (pin "9") (pinfunction "9_9") (pintype "bidirectional"))
      (node (ref "U5") (pin "N1") (pinfunction "IO_L20N_T3_34_N1") (pintype "bidirectional"))
    )
    (net (code "18") (name "FPGA_GPIO_10") (class "Default")
      (node (ref "J10") (pin "10") (pinfunction "10_10") (pintype "bidirectional"))
      (node (ref "U5") (pin "M1") (pinfunction "IO_L18P_T2_34_M1") (pintype "bidirectional"))
    )
    (net (code "19") (name "FPGA_GPIO_11") (class "Default")
      (node (ref "J10") (pin "11") (pinfunction "11_11") (pintype "bidirectional"))
      (node (ref "U5") (pin "L1") (pinfunction "IO_L18N_T2_34_L1") (pintype "bidirectional"))
    )
    (net (code "20") (name "FPGA_GPIO_12") (class "Default")
      (node (ref "J10") (pin "12") (pinfunction "12_12") (pintype "bidirectional"))
      (node (ref "U5") (pin "J2") (pinfunction "IO_L15P_T2_DQS_34_J2") (pintype "bidirectional"))
    )
    (net (code "21") (name "FPGA_GPIO_13") (class "Default")
      (node (ref "J10") (pin "13") (pinfunction "13_13") (pintype "bidirectional"))
      (node (ref "U5") (pin "P2") (pinfunction "IO_L20P_T3_34_P2") (pintype "bidirectional"))
    )
    (net (code "22") (name "FPGA_GPIO_14") (class "Default")
      (node (ref "J10") (pin "14") (pinfunction "14_14") (pintype "bidirectional"))
      (node (ref "U5") (pin "P3") (pinfunction "IO_L21N_T3_DQS_34_P3") (pintype "bidirectional"))
    )
    (net (code "23") (name "FPGA_GPIO_15") (class "Default")
      (node (ref "J10") (pin "15") (pinfunction "15_15") (pintype "bidirectional"))
      (node (ref "U5") (pin "P4") (pinfunction "IO_L21P_T3_DQS_34_P4") (pintype "bidirectional"))
    )
    (net (code "24") (name "FPGA_GPIO_16") (class "Default")
      (node (ref "J10") (pin "16") (pinfunction "16_16") (pintype "bidirectional"))
      (node (ref "U5") (pin "P5") (pinfunction "IO_L24P_T3_34_P5") (pintype "bidirectional"))
    )
    (net (code "25") (name "FPGA_GPIO_17") (class "Default")
      (node (ref "J10") (pin "17") (pinfunction "17_17") (pintype "bidirectional"))
      (node (ref "U5") (pin "L5") (pinfunction "IO_25_34_L5") (pintype "bidirectional"))
    )
    (net (code "26") (name "FPGA_GPIO_18") (class "Default")
      (node (ref "J10") (pin "18") (pinfunction "18_18") (pintype "bidirectional"))
      (node (ref "U5") (pin "N10") (pinfunction "IO_L23P_T3_D19_14_N10") (pintype "bidirectional"))
    )
    (net (code "27") (name "FPGA_GPIO_19") (class "Default")
      (node (ref "J10") (pin "19") (pinfunction "19_19") (pintype "bidirectional"))
      (node (ref "U5") (pin "H11") (pinfunction "IO_L13P_T2_MRCC_14_H11") (pintype "bidirectional"))
    )
    (net (code "28") (name "FPGA_GPIO_20") (class "Default")
      (node (ref "J10") (pin "20") (pinfunction "20_20") (pintype "bidirectional"))
      (node (ref "U5") (pin "H12") (pinfunction "IO_L13N_T2_MRCC_14_H12") (pintype "bidirectional"))
    )
    (net (code "29") (name "FPGA_INT_POWER") (class "Default")
      (node (ref "M1") (pin "4") (pinfunction "G_4") (pintype "bidirectional"))
      (node (ref "U1") (pin "10") (pinfunction "(SS/PCINT0)PB0_10") (pintype "bidirectional"))
    )
    (net (code "30") (name "FPGA_IO_POWER") (class "Default")
      (node (ref "M3") (pin "4") (pinfunction "G_4") (pintype "bidirectional"))
      (node (ref "U1") (pin "2") (pinfunction "(INT.7/AIN.1/UVCON)PE7_2") (pintype "bidirectional"))
    )
    (net (code "31") (name "FPGA_LED0") (class "Default")
      (node (ref "R18") (pin "1") (pinfunction "1_1") (pintype "bidirectional"))
      (node (ref "U5") (pin "A2") (pinfunction "IO_L3N_T0_DQS_34_A2") (pintype "bidirectional"))
    )
    (net (code "32") (name "FPGA_LED1") (class "Default")
      (node (ref "R19") (pin "1") (pinfunction "1_1") (pintype "bidirectional"))
      (node (ref "U5") (pin "A3") (pinfunction "IO_L2N_T0_34_A3") (pintype "bidirectional"))
    )
    (net (code "33") (name "FPGA_LED2") (class "Default")
      (node (ref "R20") (pin "1") (pinfunction "1_1") (pintype "bidirectional"))
      (node (ref "U5") (pin "A4") (pinfunction "IO_L2P_T0_34_A4") (pintype "bidirectional"))
    )
    (net (code "34") (name "FPGA_LED3") (class "Default")
      (node (ref "R22") (pin "1") (pinfunction "1_1") (pintype "bidirectional"))
      (node (ref "U5") (pin "A5") (pinfunction "IO_L4N_T0_34_A5") (pintype "bidirectional"))
    )
    (net (code "35") (name "FPGA_RESET") (class "Default")
      (node (ref "R28") (pin "1") (pinfunction "1_1") (pintype "bidirectional"))
      (node (ref "S3") (pin "2") (pinfunction "3_2") (pintype "bidirectional"))
      (node (ref "U1") (pin "59") (pinfunction "PF2(ADC2)_59") (pintype "bidirectional"))
      (node (ref "U5") (pin "L7") (pinfunction "PROGRAM_B_0_L7") (pintype "bidirectional"))
    )
    (net (code "36") (name "FPGA_VCCAUX") (class "Default")
      (node (ref "C12") (pin "1") (pinfunction "P$1_1") (pintype "bidirectional"))
      (node (ref "C13") (pin "1") (pinfunction "P$1_1") (pintype "bidirectional"))
      (node (ref "C14") (pin "1") (pinfunction "P$1_1") (pintype "bidirectional"))
      (node (ref "C15") (pin "1") (pinfunction "P$1_1") (pintype "bidirectional"))
      (node (ref "C16") (pin "1") (pinfunction "P$1_1") (pintype "bidirectional"))
      (node (ref "M2") (pin "5") (pinfunction "D_5") (pintype "bidirectional"))
      (node (ref "M2") (pin "6") (pinfunction "D_6") (pintype "bidirectional"))
      (node (ref "M2") (pin "7") (pinfunction "D_7") (pintype "bidirectional"))
      (node (ref "M2") (pin "8") (pinfunction "D_8") (pintype "bidirectional"))
      (node (ref "U5") (pin "F10") (pinfunction "VCCAUX_F10") (pintype "bidirectional"))
      (node (ref "U5") (pin "H10") (pinfunction "VCCAUX_H10") (pintype "bidirectional"))
      (node (ref "U5") (pin "K10") (pinfunction "VCCAUX_K10") (pintype "bidirectional"))
      (node (ref "U5") (pin "L9") (pinfunction "VCCAUX_L9") (pintype "bidirectional"))
      (node (ref "U5") (pin "N7") (pinfunction "CFGBVS_0_N7") (pintype "bidirectional"))
    )
    (net (code "37") (name "FPGA_VCCAUX_MON") (class "Default")
      (node (ref "M2") (pin "1") (pinfunction "S_1") (pintype "bidirectional"))
      (node (ref "M2") (pin "2") (pinfunction "S_2") (pintype "bidirectional"))
      (node (ref "M2") (pin "3") (pinfunction "S_3") (pintype "bidirectional"))
      (node (ref "R38") (pin "1") (pinfunction "1_1") (pintype "bidirectional"))
      (node (ref "U10") (pin "2") (pinfunction "SENSE1-_2") (pintype "bidirectional"))
    )
    (net (code "38") (name "FPGA_VCCINT") (class "Default")
      (node (ref "C10") (pin "1") (pinfunction "P$1_1") (pintype "bidirectional"))
      (node (ref "C11") (pin "1") (pinfunction "P$1_1") (pintype "bidirectional"))
      (node (ref "C7") (pin "1") (pinfunction "P$1_1") (pintype "bidirectional"))
      (node (ref "C8") (pin "1") (pinfunction "P$1_1") (pintype "bidirectional"))
      (node (ref "C9") (pin "1") (pinfunction "P$1_1") (pintype "bidirectional"))
      (node (ref "M1") (pin "5") (pinfunction "D_5") (pintype "bidirectional"))
      (node (ref "M1") (pin "6") (pinfunction "D_6") (pintype "bidirectional"))
      (node (ref "M1") (pin "7") (pinfunction "D_7") (pintype "bidirectional"))
      (node (ref "M1") (pin "8") (pinfunction "D_8") (pintype "bidirectional"))
      (node (ref "U5") (pin "D6") (pinfunction "VCCINT_D6") (pintype "bidirectional"))
      (node (ref "U5") (pin "D8") (pinfunction "VCCINT_D8") (pintype "bidirectional"))
      (node (ref "U5") (pin "E5") (pinfunction "VCCBRAM_E5") (pintype "bidirectional"))
      (node (ref "U5") (pin "E7") (pinfunction "VCCINT_E7") (pintype "bidirectional"))
      (node (ref "U5") (pin "E9") (pinfunction "VCCINT_E9") (pintype "bidirectional"))
      (node (ref "U5") (pin "F6") (pinfunction "VCCINT_F6") (pintype "bidirectional"))
      (node (ref "U5") (pin "G5") (pinfunction "VCCBRAM_G5") (pintype "bidirectional"))
      (node (ref "U5") (pin "G9") (pinfunction "VCCINT_G9") (pintype "bidirectional"))
      (node (ref "U5") (pin "H6") (pinfunction "VCCINT_H6") (pintype "bidirectional"))
      (node (ref "U5") (pin "J5") (pinfunction "VCCBRAM_J5") (pintype "bidirectional"))
      (node (ref "U5") (pin "J9") (pinfunction "VCCINT_J9") (pintype "bidirectional"))
      (node (ref "U5") (pin "K6") (pinfunction "VCCINT_K6") (pintype "bidirectional"))
      (node (ref "U5") (pin "K8") (pinfunction "VCCINT_K8") (pintype "bidirectional"))
    )
    (net (code "39") (name "FPGA_VCCINT_MON") (class "Default")
      (node (ref "M1") (pin "1") (pinfunction "S_1") (pintype "bidirectional"))
      (node (ref "M1") (pin "2") (pinfunction "S_2") (pintype "bidirectional"))
      (node (ref "M1") (pin "3") (pinfunction "S_3") (pintype "bidirectional"))
      (node (ref "R40") (pin "1") (pinfunction "1_1") (pintype "bidirectional"))
      (node (ref "U10") (pin "4") (pinfunction "SENSE2-_4") (pintype "bidirectional"))
    )
    (net (code "40") (name "FPGA_VCCIO") (class "Default")
      (node (ref "C17") (pin "1") (pinfunction "P$1_1") (pintype "bidirectional"))
      (node (ref "C18") (pin "1") (pinfunction "P$1_1") (pintype "bidirectional"))
      (node (ref "C19") (pin "1") (pinfunction "P$1_1") (pintype "bidirectional"))
      (node (ref "C20") (pin "1") (pinfunction "P$1_1") (pintype "bidirectional"))
      (node (ref "C21") (pin "1") (pinfunction "P$1_1") (pintype "bidirectional"))
      (node (ref "C22") (pin "1") (pinfunction "P$1_1") (pintype "bidirectional"))
      (node (ref "C23") (pin "1") (pinfunction "P$1_1") (pintype "bidirectional"))
      (node (ref "J9") (pin "1") (pinfunction "REF_1") (pintype "bidirectional"))
      (node (ref "M3") (pin "5") (pinfunction "D_5") (pintype "bidirectional"))
      (node (ref "M3") (pin "6") (pinfunction "D_6") (pintype "bidirectional"))
      (node (ref "M3") (pin "7") (pinfunction "D_7") (pintype "bidirectional"))
      (node (ref "M3") (pin "8") (pinfunction "D_8") (pintype "bidirectional"))
      (node (ref "R21") (pin "2") (pinfunction "2_2") (pintype "bidirectional"))
      (node (ref "R23") (pin "2") (pinfunction "2_2") (pintype "bidirectional"))
      (node (ref "R24") (pin "1") (pinfunction "1_1") (pintype "bidirectional"))
      (node (ref "R25") (pin "1") (pinfunction "1_1") (pintype "bidirectional"))
      (node (ref "R26") (pin "1") (pinfunction "1_1") (pintype "bidirectional"))
      (node (ref "R28") (pin "2") (pinfunction "2_2") (pintype "bidirectional"))
      (node (ref "U5") (pin "G13") (pinfunction "VCCO_14_G13") (pintype "bidirectional"))
      (node (ref "U5") (pin "G2") (pinfunction "VCCO_34_G2") (pintype "bidirectional"))
      (node (ref "U5") (pin "K13") (pinfunction "VCCO_14_K13") (pintype "bidirectional"))
      (node (ref "U5") (pin "K2") (pinfunction "VCCO_34_K2") (pintype "bidirectional"))
      (node (ref "U5") (pin "N13") (pinfunction "VCCO_14_N13") (pintype "bidirectional"))
      (node (ref "U5") (pin "N2") (pinfunction "VCCO_34_N2") (pintype "bidirectional"))
      (node (ref "U5") (pin "N6") (pinfunction "VCCO_0_N6") (pintype "bidirectional"))
      (node (ref "U5") (pin "N8") (pinfunction "VCCO_0_N8") (pintype "bidirectional"))
      (node (ref "X3") (pin "4") (pinfunction "VS+_4") (pintype "bidirectional"))
      (node (ref "X4") (pin "1") (pinfunction "EN_1") (pintype "bidirectional"))
      (node (ref "X4") (pin "4") (pinfunction "VS+_4") (pintype "bidirectional"))
      (node (ref "X5") (pin "1") (pinfunction "EN_1") (pintype "bidirectional"))
      (node (ref "X5") (pin "4") (pinfunction "VS+_4") (pintype "bidirectional"))
    )
    (net (code "41") (name "FPGA_VCCIO_MON") (class "Default")
      (node (ref "M3") (pin "1") (pinfunction "S_1") (pintype "bidirectional"))
      (node (ref "M3") (pin "2") (pinfunction "S_2") (pintype "bidirectional"))
      (node (ref "M3") (pin "3") (pinfunction "S_3") (pintype "bidirectional"))
      (node (ref "R33") (pin "1") (pinfunction "1_1") (pintype "bidirectional"))
      (node (ref "U7") (pin "4") (pinfunction "SENSE2-_4") (pintype "bidirectional"))
    )
    (net (code "42") (name "GND") (class "Default")
      (node (ref "C1") (pin "2") (pinfunction "P$2_2") (pintype "bidirectional"))
      (node (ref "C10") (pin "2") (pinfunction "P$2_2") (pintype "bidirectional"))
      (node (ref "C11") (pin "2") (pinfunction "P$2_2") (pintype "bidirectional"))
      (node (ref "C12") (pin "2") (pinfunction "P$2_2") (pintype "bidirectional"))
      (node (ref "C13") (pin "2") (pinfunction "P$2_2") (pintype "bidirectional"))
      (node (ref "C14") (pin "2") (pinfunction "P$2_2") (pintype "bidirectional"))
      (node (ref "C15") (pin "2") (pinfunction "P$2_2") (pintype "bidirectional"))
      (node (ref "C16") (pin "2") (pinfunction "P$2_2") (pintype "bidirectional"))
      (node (ref "C17") (pin "2") (pinfunction "P$2_2") (pintype "bidirectional"))
      (node (ref "C18") (pin "2") (pinfunction "P$2_2") (pintype "bidirectional"))
      (node (ref "C19") (pin "2") (pinfunction "P$2_2") (pintype "bidirectional"))
      (node (ref "C2") (pin "2") (pinfunction "P$2_2") (pintype "bidirectional"))
      (node (ref "C20") (pin "2") (pinfunction "P$2_2") (pintype "bidirectional"))
      (node (ref "C21") (pin "2") (pinfunction "P$2_2") (pintype "bidirectional"))
      (node (ref "C22") (pin "2") (pinfunction "P$2_2") (pintype "bidirectional"))
      (node (ref "C23") (pin "2") (pinfunction "P$2_2") (pintype "bidirectional"))
      (node (ref "C24") (pin "2") (pinfunction "P$2_2") (pintype "bidirectional"))
      (node (ref "C25") (pin "2") (pinfunction "P$2_2") (pintype "bidirectional"))
      (node (ref "C26") (pin "2") (pinfunction "P$2_2") (pintype "bidirectional"))
      (node (ref "C27") (pin "2") (pinfunction "P$2_2") (pintype "bidirectional"))
      (node (ref "C28") (pin "2") (pinfunction "P$2_2") (pintype "bidirectional"))
      (node (ref "C29") (pin "2") (pinfunction "P$2_2") (pintype "bidirectional"))
      (node (ref "C3") (pin "2") (pinfunction "P$2_2") (pintype "bidirectional"))
      (node (ref "C30") (pin "2") (pinfunction "P$2_2") (pintype "bidirectional"))
      (node (ref "C31") (pin "2") (pinfunction "P$2_2") (pintype "bidirectional"))
      (node (ref "C32") (pin "2") (pinfunction "P$2_2") (pintype "bidirectional"))
      (node (ref "C33") (pin "2") (pinfunction "P$2_2") (pintype "bidirectional"))
      (node (ref "C34") (pin "2") (pinfunction "P$2_2") (pintype "bidirectional"))
      (node (ref "C35") (pin "1") (pinfunction "P$1_1") (pintype "bidirectional"))
      (node (ref "C4") (pin "2") (pinfunction "P$2_2") (pintype "bidirectional"))
      (node (ref "C5") (pin "2") (pinfunction "P$2_2") (pintype "bidirectional"))
      (node (ref "C6") (pin "2") (pinfunction "P$2_2") (pintype "bidirectional"))
      (node (ref "C7") (pin "2") (pinfunction "P$2_2") (pintype "bidirectional"))
      (node (ref "C8") (pin "2") (pinfunction "P$2_2") (pintype "bidirectional"))
      (node (ref "C9") (pin "2") (pinfunction "P$2_2") (pintype "bidirectional"))
      (node (ref "D1") (pin "2") (pinfunction "2_2") (pintype "bidirectional"))
      (node (ref "D10") (pin "2") (pinfunction "2_2") (pintype "bidirectional"))
      (node (ref "D2") (pin "2") (pinfunction "2_2") (pintype "bidirectional"))
      (node (ref "D3") (pin "2") (pinfunction "2_2") (pintype "bidirectional"))
      (node (ref "D4") (pin "2") (pinfunction "2_2") (pintype "bidirectional"))
      (node (ref "D5") (pin "2") (pinfunction "2_2") (pintype "bidirectional"))
      (node (ref "D6") (pin "2") (pinfunction "2_2") (pintype "bidirectional"))
      (node (ref "D7") (pin "2") (pinfunction "2_2") (pintype "bidirectional"))
      (node (ref "D8") (pin "2") (pinfunction "2_2") (pintype "bidirectional"))
      (node (ref "D9") (pin "2") (pinfunction "2_2") (pintype "bidirectional"))
      (node (ref "J11") (pin "5") (pinfunction "GND_5") (pintype "bidirectional"))
      (node (ref "J2") (pin "7") (pinfunction "7_7") (pintype "bidirectional"))
      (node (ref "J2") (pin "8") (pinfunction "8_8") (pintype "bidirectional"))
      (node (ref "J3") (pin "6") (pinfunction "GND_6") (pintype "bidirectional"))
      (node (ref "J5") (pin "2") (pinfunction "2_2") (pintype "bidirectional"))
      (node (ref "J6") (pin "6") (pinfunction "GND_6") (pintype "bidirectional"))
      (node (ref "J7") (pin "2") (pinfunction "2_2") (pintype "bidirectional"))
      (node (ref "J8") (pin "5") (pinfunction "GND_5") (pintype "bidirectional"))
      (node (ref "J9") (pin "2") (pinfunction "GND_2") (pintype "bidirectional"))
      (node (ref "R35") (pin "1") (pinfunction "1_1") (pintype "bidirectional"))
      (node (ref "R36") (pin "1") (pinfunction "1_1") (pintype "bidirectional"))
      (node (ref "R41") (pin "1") (pinfunction "1_1") (pintype "bidirectional"))
      (node (ref "R42") (pin "1") (pinfunction "1_1") (pintype "bidirectional"))
      (node (ref "R46") (pin "2") (pinfunction "2_2") (pintype "bidirectional"))
      (node (ref "R47") (pin "2") (pinfunction "2_2") (pintype "bidirectional"))
      (node (ref "R48") (pin "1") (pinfunction "1_1") (pintype "bidirectional"))
      (node (ref "R49") (pin "1") (pinfunction "1_1") (pintype "bidirectional"))
      (node (ref "S1") (pin "1") (pinfunction "1_1") (pintype "bidirectional"))
      (node (ref "S2") (pin "5") (pinfunction "4Y_5") (pintype "bidirectional"))
      (node (ref "S2") (pin "6") (pinfunction "3Y_6") (pintype "bidirectional"))
      (node (ref "S2") (pin "7") (pinfunction "2Y_7") (pintype "bidirectional"))
      (node (ref "S2") (pin "8") (pinfunction "1Y_8") (pintype "bidirectional"))
      (node (ref "S3") (pin "1") (pinfunction "1_1") (pintype "bidirectional"))
      (node (ref "TP5") (pin "3") (pinfunction ">NAME_3") (pintype "bidirectional"))
      (node (ref "U1") (pin "22") (pinfunction "GND_22") (pintype "bidirectional"))
      (node (ref "U1") (pin "53") (pinfunction "GND_53") (pintype "bidirectional"))
      (node (ref "U1") (pin "6") (pinfunction "UGND_6") (pintype "bidirectional"))
      (node (ref "U1") (pin "63") (pinfunction "GND_63") (pintype "bidirectional"))
      (node (ref "U1") (pin "PAD") (pinfunction "GND_PAD") (pintype "bidirectional"))
      (node (ref "U1") (pin "VIA1") (pinfunction "GND_VIA1") (pintype "bidirectional"))
      (node (ref "U1") (pin "VIA2") (pinfunction "GND_VIA2") (pintype "bidirectional"))
      (node (ref "U1") (pin "VIA3") (pinfunction "GND_VIA3") (pintype "bidirectional"))
      (node (ref "U1") (pin "VIA4") (pinfunction "GND_VIA4") (pintype "bidirectional"))
      (node (ref "U1") (pin "VIA5") (pinfunction "GND_VIA5") (pintype "bidirectional"))
      (node (ref "U1") (pin "VIA6") (pinfunction "GND_VIA6") (pintype "bidirectional"))
      (node (ref "U1") (pin "VIA7") (pinfunction "GND_VIA7") (pintype "bidirectional"))
      (node (ref "U1") (pin "VIA8") (pinfunction "GND_VIA8") (pintype "bidirectional"))
      (node (ref "U1") (pin "VIA9") (pinfunction "GND_VIA9") (pintype "bidirectional"))
      (node (ref "U10") (pin "5") (pinfunction "GND_5") (pintype "bidirectional"))
      (node (ref "U10") (pin "P$1") (pinfunction "GND_P$1") (pintype "bidirectional"))
      (node (ref "U10") (pin "P$2") (pinfunction "GND_P$2") (pintype "bidirectional"))
      (node (ref "U10") (pin "P$3") (pinfunction "GND_P$3") (pintype "bidirectional"))
      (node (ref "U10") (pin "P$4") (pinfunction "GND_P$4") (pintype "bidirectional"))
      (node (ref "U11") (pin "9") (pinfunction "GND_9") (pintype "bidirectional"))
      (node (ref "U12") (pin "9") (pinfunction "GND_9") (pintype "bidirectional"))
      (node (ref "U13") (pin "1") (pinfunction "_OE_1") (pintype "bidirectional"))
      (node (ref "U13") (pin "10") (pinfunction "GND_10") (pintype "bidirectional"))
      (node (ref "U2") (pin "1") (pinfunction "GND_1") (pintype "bidirectional"))
      (node (ref "U2") (pin "11") (pinfunction "GND_11") (pintype "bidirectional"))
      (node (ref "U2") (pin "12") (pinfunction "GND_12") (pintype "bidirectional"))
      (node (ref "U3") (pin "15") (pinfunction "GND_15") (pintype "bidirectional"))
      (node (ref "U3") (pin "23") (pinfunction "GND_23") (pintype "bidirectional"))
      (node (ref "U3") (pin "35") (pinfunction "GND_35") (pintype "bidirectional"))
      (node (ref "U3") (pin "43") (pinfunction "GND_43") (pintype "bidirectional"))
      (node (ref "U3") (pin "45") (pinfunction "GND_45") (pintype "bidirectional"))
      (node (ref "U3") (pin "5") (pinfunction "UGND_5") (pintype "bidirectional"))
      (node (ref "U4") (pin "10") (pinfunction "LB_L_10") (pintype "bidirectional"))
      (node (ref "U4") (pin "12") (pinfunction "CE0_L_12") (pintype "bidirectional"))
      (node (ref "U4") (pin "18") (pinfunction "GND_18") (pintype "bidirectional"))
      (node (ref "U4") (pin "19") (pinfunction "GND_19") (pintype "bidirectional"))
      (node (ref "U4") (pin "35") (pinfunction "GND_35") (pintype "bidirectional"))
      (node (ref "U4") (pin "38") (pinfunction "GND_38") (pintype "bidirectional"))
      (node (ref "U4") (pin "57") (pinfunction "GND_57") (pintype "bidirectional"))
      (node (ref "U4") (pin "58") (pinfunction "GND_58") (pintype "bidirectional"))
      (node (ref "U4") (pin "61") (pinfunction "GND_61") (pintype "bidirectional"))
      (node (ref "U4") (pin "64") (pinfunction "CE0_R_64") (pintype "bidirectional"))
      (node (ref "U4") (pin "66") (pinfunction "LB_R_66") (pintype "bidirectional"))
      (node (ref "U4") (pin "87") (pinfunction "MS_87") (pintype "bidirectional"))
      (node (ref "U4") (pin "88") (pinfunction "GND_88") (pintype "bidirectional"))
      (node (ref "U5") (pin "A1") (pinfunction "GND_A1") (pintype "bidirectional"))
      (node (ref "U5") (pin "A11") (pinfunction "GND_A11") (pintype "bidirectional"))
      (node (ref "U5") (pin "A14") (pinfunction "GND_A14") (pintype "bidirectional"))
      (node (ref "U5") (pin "A6") (pinfunction "GND_A6") (pintype "bidirectional"))
      (node (ref "U5") (pin "A9") (pinfunction "GND_A9") (pintype "bidirectional"))
      (node (ref "U5") (pin "B4") (pinfunction "GND_B4") (pintype "bidirectional"))
      (node (ref "U5") (pin "B7") (pinfunction "GND_B7") (pintype "bidirectional"))
      (node (ref "U5") (pin "B9") (pinfunction "GND_B9") (pintype "bidirectional"))
      (node (ref "U5") (pin "C13") (pinfunction "GND_C13") (pintype "bidirectional"))
      (node (ref "U5") (pin "C2") (pinfunction "GND_C2") (pintype "bidirectional"))
      (node (ref "U5") (pin "C6") (pinfunction "GND_C6") (pintype "bidirectional"))
      (node (ref "U5") (pin "C7") (pinfunction "GND_C7") (pintype "bidirectional"))
      (node (ref "U5") (pin "C8") (pinfunction "GND_C8") (pintype "bidirectional"))
      (node (ref "U5") (pin "C9") (pinfunction "GND_C9") (pintype "bidirectional"))
      (node (ref "U5") (pin "D11") (pinfunction "GND_D11") (pintype "bidirectional"))
      (node (ref "U5") (pin "D5") (pinfunction "GND_D5") (pintype "bidirectional"))
      (node (ref "U5") (pin "D7") (pinfunction "GND_D7") (pintype "bidirectional"))
      (node (ref "U5") (pin "D9") (pinfunction "GND_D9") (pintype "bidirectional"))
      (node (ref "U5") (pin "E1") (pinfunction "GND_E1") (pintype "bidirectional"))
      (node (ref "U5") (pin "E10") (pinfunction "GND_E10") (pintype "bidirectional"))
      (node (ref "U5") (pin "E14") (pinfunction "GND_E14") (pintype "bidirectional"))
      (node (ref "U5") (pin "E3") (pinfunction "GND_E3") (pintype "bidirectional"))
      (node (ref "U5") (pin "E6") (pinfunction "GND_E6") (pintype "bidirectional"))
      (node (ref "U5") (pin "E8") (pinfunction "GND_E8") (pintype "bidirectional"))
      (node (ref "U5") (pin "F5") (pinfunction "GND_F5") (pintype "bidirectional"))
      (node (ref "U5") (pin "F9") (pinfunction "GND_F9") (pintype "bidirectional"))
      (node (ref "U5") (pin "G10") (pinfunction "GND_G10") (pintype "bidirectional"))
      (node (ref "U5") (pin "G12") (pinfunction "GND_G12") (pintype "bidirectional"))
      (node (ref "U5") (pin "G3") (pinfunction "GND_G3") (pintype "bidirectional"))
      (node (ref "U5") (pin "G6") (pinfunction "GND_G6") (pintype "bidirectional"))
      (node (ref "U5") (pin "H5") (pinfunction "GND_H5") (pintype "bidirectional"))
      (node (ref "U5") (pin "H9") (pinfunction "GND_H9") (pintype "bidirectional"))
      (node (ref "U5") (pin "J10") (pinfunction "GND_J10") (pintype "bidirectional"))
      (node (ref "U5") (pin "J6") (pinfunction "GND_J6") (pintype "bidirectional"))
      (node (ref "U5") (pin "J7") (pinfunction "DXN_0_J7") (pintype "bidirectional"))
      (node (ref "U5") (pin "J8") (pinfunction "DXP_0_J8") (pintype "bidirectional"))
      (node (ref "U5") (pin "K1") (pinfunction "GND_K1") (pintype "bidirectional"))
      (node (ref "U5") (pin "K14") (pinfunction "GND_K14") (pintype "bidirectional"))
      (node (ref "U5") (pin "K5") (pinfunction "GND_K5") (pintype "bidirectional"))
      (node (ref "U5") (pin "K7") (pinfunction "GND_K7") (pintype "bidirectional"))
      (node (ref "U5") (pin "K9") (pinfunction "GND_K9") (pintype "bidirectional"))
      (node (ref "U5") (pin "L10") (pinfunction "GND_L10") (pintype "bidirectional"))
      (node (ref "U5") (pin "L11") (pinfunction "GND_L11") (pintype "bidirectional"))
      (node (ref "U5") (pin "L12") (pinfunction "IO_L16P_T2_CSI_B_14_L12") (pintype "bidirectional"))
      (node (ref "U5") (pin "L4") (pinfunction "GND_L4") (pintype "bidirectional"))
      (node (ref "U5") (pin "L6") (pinfunction "GND_L6") (pintype "bidirectional"))
      (node (ref "U5") (pin "L8") (pinfunction "GND_L8") (pintype "bidirectional"))
      (node (ref "U5") (pin "M13") (pinfunction "IO_L15P_T2_DQS_RDWR_B_14_M13") (pintype "bidirectional"))
      (node (ref "U5") (pin "N12") (pinfunction "GND_N12") (pintype "bidirectional"))
      (node (ref "U5") (pin "N3") (pinfunction "GND_N3") (pintype "bidirectional"))
      (node (ref "U5") (pin "N5") (pinfunction "GND_N5") (pintype "bidirectional"))
      (node (ref "U5") (pin "N9") (pinfunction "GND_N9") (pintype "bidirectional"))
      (node (ref "U5") (pin "P1") (pinfunction "GND_P1") (pintype "bidirectional"))
      (node (ref "U5") (pin "P14") (pinfunction "GND_P14") (pintype "bidirectional"))
      (node (ref "U6") (pin "4") (pinfunction "VSS_4") (pintype "bidirectional"))
      (node (ref "U7") (pin "5") (pinfunction "GND_5") (pintype "bidirectional"))
      (node (ref "U7") (pin "P$1") (pinfunction "GND_P$1") (pintype "bidirectional"))
      (node (ref "U7") (pin "P$2") (pinfunction "GND_P$2") (pintype "bidirectional"))
      (node (ref "U7") (pin "P$3") (pinfunction "GND_P$3") (pintype "bidirectional"))
      (node (ref "U7") (pin "P$4") (pinfunction "GND_P$4") (pintype "bidirectional"))
      (node (ref "U8") (pin "5") (pinfunction "GND_5") (pintype "bidirectional"))
      (node (ref "U8") (pin "P$1") (pinfunction "GND_P$1") (pintype "bidirectional"))
      (node (ref "U8") (pin "P$2") (pinfunction "GND_P$2") (pintype "bidirectional"))
      (node (ref "U8") (pin "P$3") (pinfunction "GND_P$3") (pintype "bidirectional"))
      (node (ref "U8") (pin "P$4") (pinfunction "GND_P$4") (pintype "bidirectional"))
      (node (ref "U9") (pin "5") (pinfunction "GND_5") (pintype "bidirectional"))
      (node (ref "U9") (pin "P$1") (pinfunction "GND_P$1") (pintype "bidirectional"))
      (node (ref "U9") (pin "P$2") (pinfunction "GND_P$2") (pintype "bidirectional"))
      (node (ref "U9") (pin "P$3") (pinfunction "GND_P$3") (pintype "bidirectional"))
      (node (ref "U9") (pin "P$4") (pinfunction "GND_P$4") (pintype "bidirectional"))
      (node (ref "X3") (pin "2") (pinfunction "GND_2") (pintype "bidirectional"))
      (node (ref "X4") (pin "2") (pinfunction "GND_2") (pintype "bidirectional"))
      (node (ref "X5") (pin "2") (pinfunction "GND_2") (pintype "bidirectional"))
    )
    (net (code "43") (name "INIT_B") (class "Default")
      (node (ref "R21") (pin "1") (pinfunction "1_1") (pintype "bidirectional"))
      (node (ref "U1") (pin "58") (pinfunction "PF3(ADC3)_58") (pintype "bidirectional"))
      (node (ref "U5") (pin "P8") (pinfunction "INIT_B_0_P8") (pintype "bidirectional"))
    )
    (net (code "44") (name "JTAG_TCK") (class "Default")
      (node (ref "J9") (pin "3") (pinfunction "TCK_3") (pintype "bidirectional"))
      (node (ref "U1") (pin "57") (pinfunction "PF4(ADC4/TCK)_57") (pintype "bidirectional"))
      (node (ref "U5") (pin "A7") (pinfunction "TCK_0_A7") (pintype "bidirectional"))
    )
    (net (code "45") (name "JTAG_TDI") (class "Default")
      (node (ref "J9") (pin "5") (pinfunction "TDI_5") (pintype "bidirectional"))
      (node (ref "U1") (pin "54") (pinfunction "PF7(ADC7/TDI)_54") (pintype "bidirectional"))
      (node (ref "U5") (pin "P7") (pinfunction "TDI_0_P7") (pintype "bidirectional"))
    )
    (net (code "46") (name "JTAG_TDO") (class "Default")
      (node (ref "J9") (pin "4") (pinfunction "TDO_4") (pintype "bidirectional"))
      (node (ref "U1") (pin "55") (pinfunction "PF6(ADC6/TDO)_55") (pintype "bidirectional"))
      (node (ref "U5") (pin "P6") (pinfunction "TDO_0_P6") (pintype "bidirectional"))
    )
    (net (code "47") (name "JTAG_TMS") (class "Default")
      (node (ref "J9") (pin "6") (pinfunction "TMS_6") (pintype "bidirectional"))
      (node (ref "U1") (pin "56") (pinfunction "PF5(ADC5/TMS)_56") (pintype "bidirectional"))
      (node (ref "U5") (pin "M6") (pinfunction "TMS_0_M6") (pintype "bidirectional"))
    )
    (net (code "48") (name "MCU_LED0") (class "Default")
      (node (ref "R1") (pin "1") (pinfunction "1_1") (pintype "bidirectional"))
      (node (ref "U1") (pin "32") (pinfunction "(T0)PD7_32") (pintype "bidirectional"))
    )
    (net (code "49") (name "MCU_LED1") (class "Default")
      (node (ref "R2") (pin "1") (pinfunction "1_1") (pintype "bidirectional"))
      (node (ref "U1") (pin "31") (pinfunction "(T1)PD6_31") (pintype "bidirectional"))
    )
    (net (code "50") (name "MCU_LED2") (class "Default")
      (node (ref "R3") (pin "1") (pinfunction "1_1") (pintype "bidirectional"))
      (node (ref "U1") (pin "30") (pinfunction "(XCK1)PD5_30") (pintype "bidirectional"))
    )
    (net (code "51") (name "MCU_LED3") (class "Default")
      (node (ref "R4") (pin "1") (pinfunction "1_1") (pintype "bidirectional"))
      (node (ref "U1") (pin "29") (pinfunction "(ICP1)PD4_29") (pintype "bidirectional"))
    )
    (net (code "52") (name "MCU_RESET") (class "Default")
      (node (ref "J3") (pin "5") (pinfunction "RST_5") (pintype "bidirectional"))
      (node (ref "R8") (pin "1") (pinfunction "1_1") (pintype "bidirectional"))
      (node (ref "S1") (pin "2") (pinfunction "3_2") (pintype "bidirectional"))
      (node (ref "U1") (pin "20") (pinfunction "_RESET_20") (pintype "bidirectional"))
    )
    (net (code "53") (name "MCU_RX") (class "Default")
      (node (ref "J4") (pin "3") (pinfunction "2_3") (pintype "bidirectional"))
      (node (ref "U1") (pin "27") (pinfunction "(RXD1/INT2)PD2_27") (pintype "bidirectional"))
    )
    (net (code "54") (name "MCU_TX") (class "Default")
      (node (ref "J4") (pin "1") (pinfunction "1_1") (pintype "bidirectional"))
      (node (ref "U1") (pin "28") (pinfunction "(TXD1/INT3)PD3_28") (pintype "bidirectional"))
    )
    (net (code "55") (name "MCU_VCC") (class "Default")
      (node (ref "C1") (pin "1") (pinfunction "P$1_1") (pintype "bidirectional"))
      (node (ref "R34") (pin "1") (pinfunction "1_1") (pintype "bidirectional"))
      (node (ref "R7") (pin "1") (pinfunction "1_1") (pintype "bidirectional"))
      (node (ref "R8") (pin "2") (pinfunction "2_2") (pintype "bidirectional"))
      (node (ref "R9") (pin "1") (pinfunction "1_1") (pintype "bidirectional"))
      (node (ref "U1") (pin "21") (pinfunction "UVCC_21") (pintype "bidirectional"))
      (node (ref "U1") (pin "3") (pinfunction "UVCC_3") (pintype "bidirectional"))
      (node (ref "U1") (pin "52") (pinfunction "VCC_52") (pintype "bidirectional"))
      (node (ref "U1") (pin "62") (pinfunction "AREF_62") (pintype "bidirectional"))
      (node (ref "U1") (pin "64") (pinfunction "AVCC_64") (pintype "bidirectional"))
      (node (ref "U1") (pin "7") (pinfunction "UCAP_7") (pintype "bidirectional"))
      (node (ref "U8") (pin "4") (pinfunction "SENSE2-_4") (pintype "bidirectional"))
    )
    (net (code "56") (name "MODE0") (class "Default")
      (node (ref "R24") (pin "2") (pinfunction "2_2") (pintype "bidirectional"))
      (node (ref "S2") (pin "1") (pinfunction "1X_1") (pintype "bidirectional"))
      (node (ref "U5") (pin "M7") (pinfunction "M0_0_M7") (pintype "bidirectional"))
    )
    (net (code "57") (name "MODE1") (class "Default")
      (node (ref "R25") (pin "2") (pinfunction "2_2") (pintype "bidirectional"))
      (node (ref "S2") (pin "2") (pinfunction "2X_2") (pintype "bidirectional"))
      (node (ref "U5") (pin "M8") (pinfunction "M1_0_M8") (pintype "bidirectional"))
    )
    (net (code "58") (name "MODE2") (class "Default")
      (node (ref "R26") (pin "2") (pinfunction "2_2") (pintype "bidirectional"))
      (node (ref "S2") (pin "3") (pinfunction "3X_3") (pintype "bidirectional"))
      (node (ref "U5") (pin "M9") (pinfunction "M2_0_M9") (pintype "bidirectional"))
    )
    (net (code "59") (name "MONITORING") (class "Default")
      (node (ref "R16") (pin "2") (pinfunction "2_2") (pintype "bidirectional"))
      (node (ref "S2") (pin "4") (pinfunction "4X_4") (pintype "bidirectional"))
      (node (ref "U3") (pin "1") (pinfunction "PE6(INT6/AIN0)_1") (pintype "bidirectional"))
    )
    (net (code "60") (name "MON_HWB") (class "Default")
      (node (ref "J7") (pin "1") (pinfunction "1_1") (pintype "bidirectional"))
      (node (ref "R12") (pin "2") (pinfunction "2_2") (pintype "bidirectional"))
      (node (ref "U3") (pin "33") (pinfunction "PE2(HWB)_33") (pintype "bidirectional"))
    )
    (net (code "61") (name "MON_LED0") (class "Default")
      (node (ref "R10") (pin "1") (pinfunction "1_1") (pintype "bidirectional"))
      (node (ref "U3") (pin "20") (pinfunction "PD2(RXD1/INT2)_20") (pintype "bidirectional"))
    )
    (net (code "62") (name "MON_LED1") (class "Default")
      (node (ref "R11") (pin "1") (pinfunction "1_1") (pintype "bidirectional"))
      (node (ref "U3") (pin "21") (pinfunction "PD3(TXD1/INT3)_21") (pintype "bidirectional"))
    )
    (net (code "63") (name "MON_MISO") (class "Default")
      (node (ref "J6") (pin "1") (pinfunction "MISO_1") (pintype "bidirectional"))
      (node (ref "U3") (pin "11") (pinfunction "PB3(PDO/PCINT3/MISO)_11") (pintype "bidirectional"))
    )
    (net (code "64") (name "MON_MOSI") (class "Default")
      (node (ref "J6") (pin "4") (pinfunction "MOSI_4") (pintype "bidirectional"))
      (node (ref "U3") (pin "10") (pinfunction "PB2(PDI/PCINT2/MOSI)_10") (pintype "bidirectional"))
    )
    (net (code "65") (name "MON_RESET") (class "Default")
      (node (ref "J6") (pin "5") (pinfunction "RST_5") (pintype "bidirectional"))
      (node (ref "R17") (pin "2") (pinfunction "2_2") (pintype "bidirectional"))
      (node (ref "U3") (pin "13") (pinfunction "_RESET_13") (pintype "bidirectional"))
    )
    (net (code "66") (name "MON_SCK") (class "Default")
      (node (ref "J6") (pin "3") (pinfunction "SCK_3") (pintype "bidirectional"))
      (node (ref "U3") (pin "9") (pinfunction "PB1(PCINT1/SCL)_9") (pintype "bidirectional"))
    )
    (net (code "67") (name "MON_USB_D+") (class "Default")
      (node (ref "R15") (pin "1") (pinfunction "1_1") (pintype "bidirectional"))
      (node (ref "U3") (pin "4") (pinfunction "D+_4") (pintype "bidirectional"))
    )
    (net (code "68") (name "MON_USB_D-") (class "Default")
      (node (ref "R14") (pin "1") (pinfunction "1_1") (pintype "bidirectional"))
      (node (ref "U3") (pin "3") (pinfunction "D-_3") (pintype "bidirectional"))
    )
    (net (code "69") (name "MON_USB_VCC") (class "Default")
      (node (ref "J8") (pin "1") (pinfunction "VCC_1") (pintype "bidirectional"))
      (node (ref "U3") (pin "7") (pinfunction "VBUS_7") (pintype "bidirectional"))
    )
    (net (code "70") (name "Net-(C2-P$1)") (class "Default")
      (node (ref "C2") (pin "1") (pinfunction "P$1_1") (pintype "bidirectional"))
      (node (ref "U1") (pin "23") (pinfunction "XTAL2_23") (pintype "bidirectional"))
      (node (ref "X1") (pin "1") (pinfunction "P$1_1") (pintype "bidirectional"))
    )
    (net (code "71") (name "Net-(C3-P$1)") (class "Default")
      (node (ref "C3") (pin "1") (pinfunction "P$1_1") (pintype "bidirectional"))
      (node (ref "U1") (pin "24") (pinfunction "XTAL1_24") (pintype "bidirectional"))
      (node (ref "X1") (pin "3") (pinfunction "P$2_3") (pintype "bidirectional"))
    )
    (net (code "72") (name "Net-(C5-P$1)") (class "Default")
      (node (ref "C5") (pin "1") (pinfunction "P$1_1") (pintype "bidirectional"))
      (node (ref "U3") (pin "17") (pinfunction "XTAL1_17") (pintype "bidirectional"))
      (node (ref "X2") (pin "3") (pinfunction "P$2_3") (pintype "bidirectional"))
    )
    (net (code "73") (name "Net-(C6-P$1)") (class "Default")
      (node (ref "C6") (pin "1") (pinfunction "P$1_1") (pintype "bidirectional"))
      (node (ref "U3") (pin "16") (pinfunction "XTAL2_16") (pintype "bidirectional"))
      (node (ref "X2") (pin "1") (pinfunction "P$1_1") (pintype "bidirectional"))
    )
    (net (code "74") (name "Net-(D1-Pad1)") (class "Default")
      (node (ref "D1") (pin "1") (pinfunction "1_1") (pintype "bidirectional"))
      (node (ref "R1") (pin "2") (pinfunction "2_2") (pintype "bidirectional"))
    )
    (net (code "75") (name "Net-(D2-Pad1)") (class "Default")
      (node (ref "D2") (pin "1") (pinfunction "1_1") (pintype "bidirectional"))
      (node (ref "R2") (pin "2") (pinfunction "2_2") (pintype "bidirectional"))
    )
    (net (code "76") (name "Net-(D3-Pad1)") (class "Default")
      (node (ref "D3") (pin "1") (pinfunction "1_1") (pintype "bidirectional"))
      (node (ref "R3") (pin "2") (pinfunction "2_2") (pintype "bidirectional"))
    )
    (net (code "77") (name "Net-(D4-Pad1)") (class "Default")
      (node (ref "D4") (pin "1") (pinfunction "1_1") (pintype "bidirectional"))
      (node (ref "R4") (pin "2") (pinfunction "2_2") (pintype "bidirectional"))
    )
    (net (code "78") (name "Net-(D5-Pad1)") (class "Default")
      (node (ref "D5") (pin "1") (pinfunction "1_1") (pintype "bidirectional"))
      (node (ref "R10") (pin "2") (pinfunction "2_2") (pintype "bidirectional"))
    )
    (net (code "79") (name "Net-(D6-Pad1)") (class "Default")
      (node (ref "D6") (pin "1") (pinfunction "1_1") (pintype "bidirectional"))
      (node (ref "R11") (pin "2") (pinfunction "2_2") (pintype "bidirectional"))
    )
    (net (code "80") (name "Net-(D7-Pad1)") (class "Default")
      (node (ref "D7") (pin "1") (pinfunction "1_1") (pintype "bidirectional"))
      (node (ref "R18") (pin "2") (pinfunction "2_2") (pintype "bidirectional"))
    )
    (net (code "81") (name "Net-(D8-Pad1)") (class "Default")
      (node (ref "D8") (pin "1") (pinfunction "1_1") (pintype "bidirectional"))
      (node (ref "R19") (pin "2") (pinfunction "2_2") (pintype "bidirectional"))
    )
    (net (code "82") (name "Net-(D9-Pad1)") (class "Default")
      (node (ref "D9") (pin "1") (pinfunction "1_1") (pintype "bidirectional"))
      (node (ref "R20") (pin "2") (pinfunction "2_2") (pintype "bidirectional"))
    )
    (net (code "83") (name "Net-(D10-Pad1)") (class "Default")
      (node (ref "D10") (pin "1") (pinfunction "1_1") (pintype "bidirectional"))
      (node (ref "R22") (pin "2") (pinfunction "2_2") (pintype "bidirectional"))
    )
    (net (code "84") (name "Net-(D11-Pad2)") (class "Default")
      (node (ref "D11") (pin "2") (pinfunction "2_2") (pintype "bidirectional"))
      (node (ref "R49") (pin "2") (pinfunction "2_2") (pintype "bidirectional"))
    )
    (net (code "85") (name "Net-(J8-D+)") (class "Default")
      (node (ref "J8") (pin "3") (pinfunction "D+_3") (pintype "bidirectional"))
      (node (ref "R15") (pin "2") (pinfunction "2_2") (pintype "bidirectional"))
    )
    (net (code "86") (name "Net-(J8-D-)") (class "Default")
      (node (ref "J8") (pin "2") (pinfunction "D-_2") (pintype "bidirectional"))
      (node (ref "R14") (pin "2") (pinfunction "2_2") (pintype "bidirectional"))
    )
    (net (code "87") (name "Net-(L1-P$2)") (class "Default")
      (node (ref "L1") (pin "2") (pinfunction "P$2_2") (pintype "bidirectional"))
      (node (ref "U11") (pin "4") (pinfunction "SW1_4") (pintype "bidirectional"))
    )
    (net (code "88") (name "Net-(L2-P$1)") (class "Default")
      (node (ref "L2") (pin "1") (pinfunction "P$1_1") (pintype "bidirectional"))
      (node (ref "U12") (pin "4") (pinfunction "SW1_4") (pintype "bidirectional"))
    )
    (net (code "89") (name "Net-(L3-P$2)") (class "Default")
      (node (ref "L3") (pin "2") (pinfunction "P$2_2") (pintype "bidirectional"))
      (node (ref "U12") (pin "6") (pinfunction "SW2_6") (pintype "bidirectional"))
    )
    (net (code "90") (name "Net-(U1-D+)") (class "Default")
      (node (ref "R6") (pin "2") (pinfunction "2_2") (pintype "bidirectional"))
      (node (ref "U1") (pin "5") (pinfunction "D+_5") (pintype "bidirectional"))
    )
    (net (code "91") (name "Net-(U1-D-)") (class "Default")
      (node (ref "R5") (pin "2") (pinfunction "2_2") (pintype "bidirectional"))
      (node (ref "U1") (pin "4") (pinfunction "D-_4") (pintype "bidirectional"))
    )
    (net (code "92") (name "Net-(U3-UVCC)") (class "Default")
      (node (ref "R13") (pin "1") (pinfunction "1_1") (pintype "bidirectional"))
      (node (ref "U3") (pin "2") (pinfunction "UVCC_2") (pintype "bidirectional"))
    )
    (net (code "93") (name "Net-(U7-ADDR_SEL)") (class "Default")
      (node (ref "R35") (pin "2") (pinfunction "2_2") (pintype "bidirectional"))
      (node (ref "U7") (pin "6") (pinfunction "ADDR_SEL_6") (pintype "bidirectional"))
    )
    (net (code "94") (name "Net-(U8-ADDR_SEL)") (class "Default")
      (node (ref "R36") (pin "2") (pinfunction "2_2") (pintype "bidirectional"))
      (node (ref "U8") (pin "6") (pinfunction "ADDR_SEL_6") (pintype "bidirectional"))
    )
    (net (code "95") (name "Net-(U9-ADDR_SEL)") (class "Default")
      (node (ref "R41") (pin "2") (pinfunction "2_2") (pintype "bidirectional"))
      (node (ref "U9") (pin "6") (pinfunction "ADDR_SEL_6") (pintype "bidirectional"))
    )
    (net (code "96") (name "Net-(U10-ADDR_SEL)") (class "Default")
      (node (ref "R42") (pin "2") (pinfunction "2_2") (pintype "bidirectional"))
      (node (ref "U10") (pin "6") (pinfunction "ADDR_SEL_6") (pintype "bidirectional"))
    )
    (net (code "97") (name "Net-(U11-VFB1)") (class "Default")
      (node (ref "R43") (pin "1") (pinfunction "1_1") (pintype "bidirectional"))
      (node (ref "R46") (pin "1") (pinfunction "1_1") (pintype "bidirectional"))
      (node (ref "U11") (pin "1") (pinfunction "VFB1_1") (pintype "bidirectional"))
    )
    (net (code "98") (name "Net-(U12-VFB1)") (class "Default")
      (node (ref "R44") (pin "1") (pinfunction "1_1") (pintype "bidirectional"))
      (node (ref "R47") (pin "1") (pinfunction "1_1") (pintype "bidirectional"))
      (node (ref "U12") (pin "1") (pinfunction "VFB1_1") (pintype "bidirectional"))
    )
    (net (code "99") (name "Net-(U12-VFB2)") (class "Default")
      (node (ref "R45") (pin "2") (pinfunction "2_2") (pintype "bidirectional"))
      (node (ref "R48") (pin "2") (pinfunction "2_2") (pintype "bidirectional"))
      (node (ref "U12") (pin "8") (pinfunction "VFB2_8") (pintype "bidirectional"))
    )
    (net (code "100") (name "OSC_32") (class "Default")
      (node (ref "U5") (pin "G4") (pinfunction "IO_L12P_T1_MRCC_34_G4") (pintype "bidirectional"))
      (node (ref "X5") (pin "3") (pinfunction "OUTPUT_3") (pintype "bidirectional"))
    )
    (net (code "101") (name "OSC_50") (class "Default")
      (node (ref "U5") (pin "H4") (pinfunction "IO_L13P_T2_MRCC_34_H4") (pintype "bidirectional"))
      (node (ref "X4") (pin "3") (pinfunction "OUTPUT_3") (pintype "bidirectional"))
    )
    (net (code "102") (name "OSC_100") (class "Default")
      (node (ref "U5") (pin "A10") (pinfunction "IO_L3N_T0_DQS_EMCCLK_14_A10") (pintype "bidirectional"))
      (node (ref "X3") (pin "3") (pinfunction "OUTPUT_3") (pintype "bidirectional"))
    )
    (net (code "103") (name "SCL") (class "Default")
      (node (ref "J1") (pin "1") (pinfunction "1_1") (pintype "bidirectional"))
      (node (ref "R29") (pin "1") (pinfunction "1_1") (pintype "bidirectional"))
      (node (ref "U1") (pin "25") (pinfunction "(OC0B/SCL/INT0)PD0_25") (pintype "bidirectional"))
      (node (ref "U10") (pin "9") (pinfunction "SMCLK_9") (pintype "bidirectional"))
      (node (ref "U3") (pin "18") (pinfunction "PD0(OC0B/SCL/INT0)_18") (pintype "bidirectional"))
      (node (ref "U7") (pin "9") (pinfunction "SMCLK_9") (pintype "bidirectional"))
      (node (ref "U8") (pin "9") (pinfunction "SMCLK_9") (pintype "bidirectional"))
      (node (ref "U9") (pin "9") (pinfunction "SMCLK_9") (pintype "bidirectional"))
    )
    (net (code "104") (name "SDA") (class "Default")
      (node (ref "J1") (pin "2") (pinfunction "2_2") (pintype "bidirectional"))
      (node (ref "R30") (pin "1") (pinfunction "1_1") (pintype "bidirectional"))
      (node (ref "U1") (pin "26") (pinfunction "(OC2B/SDA/INT1)PD1_26") (pintype "bidirectional"))
      (node (ref "U10") (pin "8") (pinfunction "SMDATA_8") (pintype "bidirectional"))
      (node (ref "U3") (pin "19") (pinfunction "PD1(SDA/INT1)_19") (pintype "bidirectional"))
      (node (ref "U7") (pin "8") (pinfunction "SMDATA_8") (pintype "bidirectional"))
      (node (ref "U8") (pin "8") (pinfunction "SMDATA_8") (pintype "bidirectional"))
      (node (ref "U9") (pin "8") (pinfunction "SMDATA_8") (pintype "bidirectional"))
    )
    (net (code "105") (name "SELECTMAP_D0{slash}SPI_MOSI{slash}PDI{slash}XMEGA_AD7") (class "Default")
      (node (ref "J1") (pin "5") (pinfunction "5_5") (pintype "bidirectional"))
      (node (ref "J3") (pin "4") (pinfunction "MOSI_4") (pintype "bidirectional"))
      (node (ref "U1") (pin "12") (pinfunction "(PDI/PCINT2/MOSI)PB2_12") (pintype "bidirectional"))
      (node (ref "U1") (pin "44") (pinfunction "PA7(AD7)_44") (pintype "bidirectional"))
      (node (ref "U13") (pin "9") (pinfunction "D7_9") (pintype "bidirectional"))
      (node (ref "U2") (pin "5") (pinfunction "SDI_5") (pintype "bidirectional"))
      (node (ref "U4") (pin "29") (pinfunction "D7_L_29") (pintype "bidirectional"))
      (node (ref "U5") (pin "B11") (pinfunction "IO_L1P_T0_D00_MOSI_14_B11") (pintype "bidirectional"))
      (node (ref "U6") (pin "5") (pinfunction "SI_5") (pintype "bidirectional"))
    )
    (net (code "106") (name "SELECTMAP_D1{slash}SPI_MISO{slash}MCU_PDO{slash}XMEGA_AD6") (class "Default")
      (node (ref "J1") (pin "6") (pinfunction "6_6") (pintype "bidirectional"))
      (node (ref "J3") (pin "1") (pinfunction "MISO_1") (pintype "bidirectional"))
      (node (ref "U1") (pin "13") (pinfunction "(PDO/PCINT3/MISO)PB3_13") (pintype "bidirectional"))
      (node (ref "U1") (pin "45") (pinfunction "PA6(AD6)_45") (pintype "bidirectional"))
      (node (ref "U13") (pin "8") (pinfunction "D6_8") (pintype "bidirectional"))
      (node (ref "U2") (pin "7") (pinfunction "SDO_7") (pintype "bidirectional"))
      (node (ref "U4") (pin "30") (pinfunction "D6_L_30") (pintype "bidirectional"))
      (node (ref "U5") (pin "B12") (pinfunction "IO_L1N_T0_D01_DIN_14_B12") (pintype "bidirectional"))
      (node (ref "U6") (pin "2") (pinfunction "SO_2") (pintype "bidirectional"))
    )
    (net (code "107") (name "SELECTMAP_D2{slash}FPGA_WP{slash}XMEGA_AD5") (class "Default")
      (node (ref "J1") (pin "4") (pinfunction "4_4") (pintype "bidirectional"))
      (node (ref "U1") (pin "46") (pinfunction "PA5(AD5)_46") (pintype "bidirectional"))
      (node (ref "U13") (pin "7") (pinfunction "D5_7") (pintype "bidirectional"))
      (node (ref "U4") (pin "31") (pinfunction "D5_L_31") (pintype "bidirectional"))
      (node (ref "U5") (pin "D10") (pinfunction "IO_L2P_T0_D02_14_D10") (pintype "bidirectional"))
    )
    (net (code "108") (name "SELECTMAP_D3{slash}FPGA_HOLD{slash}XMEGA_AD4") (class "Default")
      (node (ref "J1") (pin "7") (pinfunction "7_7") (pintype "bidirectional"))
      (node (ref "U1") (pin "47") (pinfunction "PA4(AD4)_47") (pintype "bidirectional"))
      (node (ref "U13") (pin "6") (pinfunction "D4_6") (pintype "bidirectional"))
      (node (ref "U4") (pin "32") (pinfunction "D4_L_32") (pintype "bidirectional"))
      (node (ref "U5") (pin "C10") (pinfunction "IO_L2N_T0_D03_14_C10") (pintype "bidirectional"))
    )
    (net (code "109") (name "SELECTMAP_D4{slash}MCU_TX1{slash}XMEGA_AD3") (class "Default")
      (node (ref "J1") (pin "3") (pinfunction "3_3") (pintype "bidirectional"))
      (node (ref "U1") (pin "48") (pinfunction "PA3(AD3)_48") (pintype "bidirectional"))
      (node (ref "U13") (pin "5") (pinfunction "D3_5") (pintype "bidirectional"))
      (node (ref "U4") (pin "33") (pinfunction "D3_L_33") (pintype "bidirectional"))
      (node (ref "U5") (pin "A12") (pinfunction "IO_L4P_T0_D04_14_A12") (pintype "bidirectional"))
    )
    (net (code "110") (name "SELECTMAP_D5{slash}MCU_RX1{slash}XMEGA_AD2") (class "Default")
      (node (ref "J1") (pin "8") (pinfunction "8_8") (pintype "bidirectional"))
      (node (ref "U1") (pin "49") (pinfunction "PA2(AD2)_49") (pintype "bidirectional"))
      (node (ref "U13") (pin "4") (pinfunction "D2_4") (pintype "bidirectional"))
      (node (ref "U4") (pin "34") (pinfunction "D2_L_34") (pintype "bidirectional"))
      (node (ref "U5") (pin "A13") (pinfunction "IO_L4N_T0_D05_14_A13") (pintype "bidirectional"))
    )
    (net (code "111") (name "SELECTMAP_D6{slash}XMEGA_AD1") (class "Default")
      (node (ref "U1") (pin "50") (pinfunction "PA1(AD1)_50") (pintype "bidirectional"))
      (node (ref "U13") (pin "3") (pinfunction "D1_3") (pintype "bidirectional"))
      (node (ref "U4") (pin "36") (pinfunction "D1_L_36") (pintype "bidirectional"))
      (node (ref "U5") (pin "B13") (pinfunction "IO_L5P_T0_D06_14_B13") (pintype "bidirectional"))
    )
    (net (code "112") (name "SELECTMAP_D7{slash}XMEGA_AD0") (class "Default")
      (node (ref "U1") (pin "51") (pinfunction "PA0(AD0)_51") (pintype "bidirectional"))
      (node (ref "U13") (pin "2") (pinfunction "D0_2") (pintype "bidirectional"))
      (node (ref "U4") (pin "37") (pinfunction "D0_L_37") (pintype "bidirectional"))
      (node (ref "U5") (pin "B14") (pinfunction "IO_L5N_T0_D07_14_B14") (pintype "bidirectional"))
    )
    (net (code "113") (name "SPI_CS") (class "Default")
      (node (ref "R27") (pin "2") (pinfunction "2_2") (pintype "bidirectional"))
      (node (ref "U1") (pin "14") (pinfunction "(PCINT4/OC.2A)PB4_14") (pintype "bidirectional"))
      (node (ref "U5") (pin "C11") (pinfunction "IO_L6P_T0_FCS_B_14_C11") (pintype "bidirectional"))
      (node (ref "U6") (pin "1") (pinfunction "CE_1") (pintype "bidirectional"))
    )
    (net (code "114") (name "SPI_SCK{slash}CCLK") (class "Default")
      (node (ref "J3") (pin "3") (pinfunction "SCK_3") (pintype "bidirectional"))
      (node (ref "U1") (pin "11") (pinfunction "(PCINT1/SCLK)PB1_11") (pintype "bidirectional"))
      (node (ref "U2") (pin "6") (pinfunction "SCK_6") (pintype "bidirectional"))
      (node (ref "U5") (pin "A8") (pinfunction "CCLK_0_A8") (pintype "bidirectional"))
      (node (ref "U6") (pin "6") (pinfunction "SCK_6") (pintype "bidirectional"))
    )
    (net (code "115") (name "SRAM_POWER") (class "Default")
      (node (ref "M4") (pin "4") (pinfunction "G_4") (pintype "bidirectional"))
      (node (ref "U1") (pin "19") (pinfunction "(INT.5/TOSC2)PE5_19") (pintype "bidirectional"))
    )
    (net (code "116") (name "SRAM_VDD") (class "Default")
      (node (ref "C24") (pin "1") (pinfunction "P$1_1") (pintype "bidirectional"))
      (node (ref "C25") (pin "1") (pinfunction "P$1_1") (pintype "bidirectional"))
      (node (ref "C26") (pin "1") (pinfunction "P$1_1") (pintype "bidirectional"))
      (node (ref "C27") (pin "1") (pinfunction "P$1_1") (pintype "bidirectional"))
      (node (ref "C28") (pin "1") (pinfunction "P$1_1") (pintype "bidirectional"))
      (node (ref "C29") (pin "1") (pinfunction "P$1_1") (pintype "bidirectional"))
      (node (ref "C30") (pin "1") (pinfunction "P$1_1") (pintype "bidirectional"))
      (node (ref "M4") (pin "5") (pinfunction "D_5") (pintype "bidirectional"))
      (node (ref "M4") (pin "6") (pinfunction "D_6") (pintype "bidirectional"))
      (node (ref "M4") (pin "7") (pinfunction "D_7") (pintype "bidirectional"))
      (node (ref "M4") (pin "8") (pinfunction "D_8") (pintype "bidirectional"))
      (node (ref "R50") (pin "2") (pinfunction "2_2") (pintype "bidirectional"))
      (node (ref "R51") (pin "2") (pinfunction "2_2") (pintype "bidirectional"))
      (node (ref "U13") (pin "20") (pinfunction "VCC_20") (pintype "bidirectional"))
      (node (ref "U4") (pin "11") (pinfunction "UB_L_11") (pintype "bidirectional"))
      (node (ref "U4") (pin "13") (pinfunction "CE1_L_13") (pintype "bidirectional"))
      (node (ref "U4") (pin "14") (pinfunction "SEM_L_14") (pintype "bidirectional"))
      (node (ref "U4") (pin "15") (pinfunction "VCC_15") (pintype "bidirectional"))
      (node (ref "U4") (pin "28") (pinfunction "VCC_28") (pintype "bidirectional"))
      (node (ref "U4") (pin "46") (pinfunction "VCC_46") (pintype "bidirectional"))
      (node (ref "U4") (pin "62") (pinfunction "SEM_R_62") (pintype "bidirectional"))
      (node (ref "U4") (pin "63") (pinfunction "CE1_R_63") (pintype "bidirectional"))
      (node (ref "U4") (pin "65") (pinfunction "UB_R_65") (pintype "bidirectional"))
    )
    (net (code "117") (name "SRAM_VDD_MON") (class "Default")
      (node (ref "M4") (pin "1") (pinfunction "S_1") (pintype "bidirectional"))
      (node (ref "M4") (pin "2") (pinfunction "S_2") (pintype "bidirectional"))
      (node (ref "M4") (pin "3") (pinfunction "S_3") (pintype "bidirectional"))
      (node (ref "R31") (pin "1") (pinfunction "1_1") (pintype "bidirectional"))
      (node (ref "U7") (pin "2") (pinfunction "SENSE1-_2") (pintype "bidirectional"))
    )
    (net (code "118") (name "UID") (class "Default")
      (node (ref "J11") (pin "4") (pinfunction "UID_4") (pintype "bidirectional"))
      (node (ref "U1") (pin "9") (pinfunction "(IUID)PE3_9") (pintype "bidirectional"))
    )
    (net (code "119") (name "USBD+") (class "Default")
      (node (ref "J11") (pin "3") (pinfunction "D+_3") (pintype "bidirectional"))
      (node (ref "R6") (pin "1") (pinfunction "1_1") (pintype "bidirectional"))
    )
    (net (code "120") (name "USBD-") (class "Default")
      (node (ref "J11") (pin "2") (pinfunction "D-_2") (pintype "bidirectional"))
      (node (ref "R5") (pin "1") (pinfunction "1_1") (pintype "bidirectional"))
    )
    (net (code "121") (name "USB_VCC_RAW") (class "Default")
      (node (ref "D11") (pin "1") (pinfunction "1_1") (pintype "bidirectional"))
      (node (ref "J11") (pin "1") (pinfunction "VCC_1") (pintype "bidirectional"))
      (node (ref "R39") (pin "1") (pinfunction "1_1") (pintype "bidirectional"))
      (node (ref "U1") (pin "8") (pinfunction "VBUS_8") (pintype "bidirectional"))
      (node (ref "U9") (pin "4") (pinfunction "SENSE2-_4") (pintype "bidirectional"))
    )
    (net (code "122") (name "WIRELESS_CS") (class "Default")
      (node (ref "R7") (pin "2") (pinfunction "2_2") (pintype "bidirectional"))
      (node (ref "U1") (pin "1") (pinfunction "(INT.6/AIN.0)PE6_1") (pintype "bidirectional"))
      (node (ref "U2") (pin "8") (pinfunction "_CS_8") (pintype "bidirectional"))
    )
    (net (code "123") (name "WIRELESS_INT") (class "Default")
      (node (ref "U1") (pin "61") (pinfunction "PF0(ADC0)_61") (pintype "bidirectional"))
      (node (ref "U2") (pin "4") (pinfunction "INT_4") (pintype "bidirectional"))
    )
    (net (code "124") (name "WIRELESS_RESET") (class "Default")
      (node (ref "U1") (pin "15") (pinfunction "(PCINT5/OC.1A)PB5_15") (pintype "bidirectional"))
      (node (ref "U2") (pin "2") (pinfunction "_RESET_2") (pintype "bidirectional"))
    )
    (net (code "125") (name "WIRELESS_VCC") (class "Default")
      (node (ref "R37") (pin "1") (pinfunction "1_1") (pintype "bidirectional"))
      (node (ref "U2") (pin "10") (pinfunction "VI_10") (pintype "bidirectional"))
      (node (ref "U9") (pin "2") (pinfunction "SENSE1-_2") (pintype "bidirectional"))
    )
    (net (code "126") (name "WIRELESS_WAKE") (class "Default")
      (node (ref "U1") (pin "60") (pinfunction "PF1(ADC1)_60") (pintype "bidirectional"))
      (node (ref "U2") (pin "3") (pinfunction "WAKE_3") (pintype "bidirectional"))
    )
    (net (code "127") (name "XFPGA_A0") (class "Default")
      (node (ref "U4") (pin "84") (pinfunction "A0_R_84") (pintype "bidirectional"))
      (node (ref "U5") (pin "E13") (pinfunction "IO_L10N_T1_D15_14_E13") (pintype "bidirectional"))
    )
    (net (code "128") (name "XFPGA_A1") (class "Default")
      (node (ref "U4") (pin "83") (pinfunction "A1_R_83") (pintype "bidirectional"))
      (node (ref "U5") (pin "E12") (pinfunction "IO_L7N_T1_D10_14_E12") (pintype "bidirectional"))
    )
    (net (code "129") (name "XFPGA_A2") (class "Default")
      (node (ref "U4") (pin "82") (pinfunction "A2_R_82") (pintype "bidirectional"))
      (node (ref "U5") (pin "E11") (pinfunction "IO_0_14_E11") (pintype "bidirectional"))
    )
    (net (code "130") (name "XFPGA_A3") (class "Default")
      (node (ref "U4") (pin "81") (pinfunction "A3_R_81") (pintype "bidirectional"))
      (node (ref "U5") (pin "F14") (pinfunction "IO_L9N_T1_DQS_D13_14_F14") (pintype "bidirectional"))
    )
    (net (code "131") (name "XFPGA_A4") (class "Default")
      (node (ref "U4") (pin "80") (pinfunction "A4_R_80") (pintype "bidirectional"))
      (node (ref "U5") (pin "F13") (pinfunction "IO_L10P_T1_D14_14_F13") (pintype "bidirectional"))
    )
    (net (code "132") (name "XFPGA_A5") (class "Default")
      (node (ref "U4") (pin "79") (pinfunction "A5_R_79") (pintype "bidirectional"))
      (node (ref "U5") (pin "F12") (pinfunction "IO_L7P_T1_D09_14_F12") (pintype "bidirectional"))
    )
    (net (code "133") (name "XFPGA_A6") (class "Default")
      (node (ref "U4") (pin "78") (pinfunction "A6_R_78") (pintype "bidirectional"))
      (node (ref "U5") (pin "F11") (pinfunction "IO_L12N_T1_MRCC_14_F11") (pintype "bidirectional"))
    )
    (net (code "134") (name "XFPGA_A7") (class "Default")
      (node (ref "U4") (pin "77") (pinfunction "A7_R_77") (pintype "bidirectional"))
      (node (ref "U5") (pin "G14") (pinfunction "IO_L9P_T1_DQS_14_G14") (pintype "bidirectional"))
    )
    (net (code "135") (name "XFPGA_A8") (class "Default")
      (node (ref "U4") (pin "76") (pinfunction "A8_R_76") (pintype "bidirectional"))
      (node (ref "U5") (pin "H13") (pinfunction "IO_L14P_T2_SRCC_14_H13") (pintype "bidirectional"))
    )
    (net (code "136") (name "XFPGA_A9") (class "Default")
      (node (ref "U4") (pin "75") (pinfunction "A9_R_75") (pintype "bidirectional"))
      (node (ref "U5") (pin "N14") (pinfunction "IO_L21P_T3_DQS_14_N14") (pintype "bidirectional"))
    )
    (net (code "137") (name "XFPGA_A10") (class "Default")
      (node (ref "U4") (pin "74") (pinfunction "A10_R_74") (pintype "bidirectional"))
      (node (ref "U5") (pin "N11") (pinfunction "IO_L23N_T3_D18_14_N11") (pintype "bidirectional"))
    )
    (net (code "138") (name "XFPGA_A11") (class "Default")
      (node (ref "U4") (pin "73") (pinfunction "A11_R_73") (pintype "bidirectional"))
      (node (ref "U5") (pin "M14") (pinfunction "IO_L21N_T3_DQS_D22_14_M14") (pintype "bidirectional"))
    )
    (net (code "139") (name "XFPGA_A12") (class "Default")
      (node (ref "U4") (pin "72") (pinfunction "A12_R_72") (pintype "bidirectional"))
      (node (ref "U5") (pin "M12") (pinfunction "IO_L20N_T3_D23_14_M12") (pintype "bidirectional"))
    )
    (net (code "140") (name "XFPGA_A13") (class "Default")
      (node (ref "U4") (pin "71") (pinfunction "A13_R_71") (pintype "bidirectional"))
      (node (ref "U5") (pin "M11") (pinfunction "IO_L20P_T3_D24_14_M11") (pintype "bidirectional"))
    )
    (net (code "141") (name "XFPGA_A14") (class "Default")
      (node (ref "U4") (pin "70") (pinfunction "A14_R_70") (pintype "bidirectional"))
      (node (ref "U5") (pin "M10") (pinfunction "IO_25_14_M10") (pintype "bidirectional"))
    )
    (net (code "142") (name "XFPGA_A15") (class "Default")
      (node (ref "U4") (pin "69") (pinfunction "A15_R_69") (pintype "bidirectional"))
      (node (ref "U5") (pin "L14") (pinfunction "IO_L15N_T2_DQS_DOUT_CSO_B_14_L14") (pintype "bidirectional"))
    )
    (net (code "143") (name "XFPGA_D0") (class "Default")
      (node (ref "U4") (pin "39") (pinfunction "D0_R_39") (pintype "bidirectional"))
      (node (ref "U5") (pin "D14") (pinfunction "IO_L11P_T1_SRCC_14_D14") (pintype "bidirectional"))
    )
    (net (code "144") (name "XFPGA_D1") (class "Default")
      (node (ref "U4") (pin "40") (pinfunction "D1_R_40") (pintype "bidirectional"))
      (node (ref "U5") (pin "D12") (pinfunction "IO_L8P_T1_D11_14_D12") (pintype "bidirectional"))
    )
    (net (code "145") (name "XFPGA_D2") (class "Default")
      (node (ref "U4") (pin "41") (pinfunction "D2_R_41") (pintype "bidirectional"))
      (node (ref "U5") (pin "J11") (pinfunction "IO_L17P_T2_D30_14_J11") (pintype "bidirectional"))
    )
    (net (code "146") (name "XFPGA_D3") (class "Default")
      (node (ref "U4") (pin "42") (pinfunction "D3_R_42") (pintype "bidirectional"))
      (node (ref "U5") (pin "K11") (pinfunction "IO_L19P_T3_D26_14_K11") (pintype "bidirectional"))
    )
    (net (code "147") (name "XFPGA_D4") (class "Default")
      (node (ref "U4") (pin "43") (pinfunction "D4_R_43") (pintype "bidirectional"))
      (node (ref "U5") (pin "J13") (pinfunction "IO_L18P_T2_D28_14_J13") (pintype "bidirectional"))
    )
    (net (code "148") (name "XFPGA_D5") (class "Default")
      (node (ref "U4") (pin "44") (pinfunction "D5_R_44") (pintype "bidirectional"))
      (node (ref "U5") (pin "J14") (pinfunction "IO_L18N_T2_D27_14_J14") (pintype "bidirectional"))
    )
    (net (code "149") (name "XFPGA_D6") (class "Default")
      (node (ref "U4") (pin "45") (pinfunction "D6_R_45") (pintype "bidirectional"))
      (node (ref "U5") (pin "K12") (pinfunction "IO_L19N_T3_D25_VREF_14_K12") (pintype "bidirectional"))
    )
    (net (code "150") (name "XFPGA_D7") (class "Default")
      (node (ref "U4") (pin "47") (pinfunction "D7_R_47") (pintype "bidirectional"))
      (node (ref "U5") (pin "L13") (pinfunction "IO_L16N_T2_D31_14_L13") (pintype "bidirectional"))
    )
    (net (code "151") (name "XFPGA_RD") (class "Default")
      (node (ref "U4") (pin "59") (pinfunction "OE_R_59") (pintype "bidirectional"))
      (node (ref "U5") (pin "P12") (pinfunction "IO_L22P_T3_D21_14_P12") (pintype "bidirectional"))
    )
    (net (code "152") (name "XFPGA_WR") (class "Default")
      (node (ref "R51") (pin "1") (pinfunction "1_1") (pintype "bidirectional"))
      (node (ref "U4") (pin "60") (pinfunction "RW_R_60") (pintype "bidirectional"))
      (node (ref "U5") (pin "P13") (pinfunction "IO_L22N_T3_D20_14_P13") (pintype "bidirectional"))
    )
    (net (code "153") (name "XMEGA_A0") (class "Default")
      (node (ref "U13") (pin "19") (pinfunction "Q0_19") (pintype "bidirectional"))
      (node (ref "U4") (pin "92") (pinfunction "A0_L_92") (pintype "bidirectional"))
    )
    (net (code "154") (name "XMEGA_A1") (class "Default")
      (node (ref "U13") (pin "18") (pinfunction "Q1_18") (pintype "bidirectional"))
      (node (ref "U4") (pin "93") (pinfunction "A1_L_93") (pintype "bidirectional"))
    )
    (net (code "155") (name "XMEGA_A2") (class "Default")
      (node (ref "U13") (pin "17") (pinfunction "Q2_17") (pintype "bidirectional"))
      (node (ref "U4") (pin "94") (pinfunction "A2_L_94") (pintype "bidirectional"))
    )
    (net (code "156") (name "XMEGA_A3") (class "Default")
      (node (ref "U13") (pin "16") (pinfunction "Q3_16") (pintype "bidirectional"))
      (node (ref "U4") (pin "95") (pinfunction "A3_L_95") (pintype "bidirectional"))
    )
    (net (code "157") (name "XMEGA_A4") (class "Default")
      (node (ref "U13") (pin "15") (pinfunction "Q4_15") (pintype "bidirectional"))
      (node (ref "U4") (pin "96") (pinfunction "A4_L_96") (pintype "bidirectional"))
    )
    (net (code "158") (name "XMEGA_A5") (class "Default")
      (node (ref "U13") (pin "14") (pinfunction "Q5_14") (pintype "bidirectional"))
      (node (ref "U4") (pin "97") (pinfunction "A5_L_97") (pintype "bidirectional"))
    )
    (net (code "159") (name "XMEGA_A6") (class "Default")
      (node (ref "U13") (pin "13") (pinfunction "Q6_13") (pintype "bidirectional"))
      (node (ref "U4") (pin "98") (pinfunction "A6_L_98") (pintype "bidirectional"))
    )
    (net (code "160") (name "XMEGA_A7") (class "Default")
      (node (ref "U13") (pin "12") (pinfunction "Q7_12") (pintype "bidirectional"))
      (node (ref "U4") (pin "99") (pinfunction "A7_L_99") (pintype "bidirectional"))
    )
    (net (code "161") (name "XMEGA_A8") (class "Default")
      (node (ref "J1") (pin "9") (pinfunction "9_9") (pintype "bidirectional"))
      (node (ref "U1") (pin "35") (pinfunction "PC0(A8)_35") (pintype "bidirectional"))
      (node (ref "U4") (pin "100") (pinfunction "A8_L_100") (pintype "bidirectional"))
    )
    (net (code "162") (name "XMEGA_A9") (class "Default")
      (node (ref "U1") (pin "36") (pinfunction "PC1(A9)_36") (pintype "bidirectional"))
      (node (ref "U4") (pin "1") (pinfunction "A9_L_1") (pintype "bidirectional"))
    )
    (net (code "163") (name "XMEGA_A10") (class "Default")
      (node (ref "J2") (pin "6") (pinfunction "6_6") (pintype "bidirectional"))
      (node (ref "U1") (pin "37") (pinfunction "PC2(A10)_37") (pintype "bidirectional"))
      (node (ref "U4") (pin "2") (pinfunction "A10_L_2") (pintype "bidirectional"))
    )
    (net (code "164") (name "XMEGA_A11") (class "Default")
      (node (ref "J2") (pin "5") (pinfunction "5_5") (pintype "bidirectional"))
      (node (ref "U1") (pin "38") (pinfunction "PC3(A11/T.3)_38") (pintype "bidirectional"))
      (node (ref "U4") (pin "3") (pinfunction "A11_L_3") (pintype "bidirectional"))
    )
    (net (code "165") (name "XMEGA_A12") (class "Default")
      (node (ref "J2") (pin "4") (pinfunction "4_4") (pintype "bidirectional"))
      (node (ref "U1") (pin "39") (pinfunction "PC4(A12/OC.3C)_39") (pintype "bidirectional"))
      (node (ref "U4") (pin "4") (pinfunction "A12_L_4") (pintype "bidirectional"))
    )
    (net (code "166") (name "XMEGA_A13") (class "Default")
      (node (ref "J2") (pin "3") (pinfunction "3_3") (pintype "bidirectional"))
      (node (ref "U1") (pin "40") (pinfunction "PC5(A13/OC.3B)_40") (pintype "bidirectional"))
      (node (ref "U4") (pin "5") (pinfunction "A13_L_5") (pintype "bidirectional"))
    )
    (net (code "167") (name "XMEGA_A14") (class "Default")
      (node (ref "J2") (pin "2") (pinfunction "2_2") (pintype "bidirectional"))
      (node (ref "U1") (pin "41") (pinfunction "PC6(A14/OC.3A)_41") (pintype "bidirectional"))
      (node (ref "U4") (pin "6") (pinfunction "A14_L_6") (pintype "bidirectional"))
    )
    (net (code "168") (name "XMEGA_A15") (class "Default")
      (node (ref "J2") (pin "1") (pinfunction "1_1") (pintype "bidirectional"))
      (node (ref "U1") (pin "42") (pinfunction "PC7(A15/IC.3/CLKO)_42") (pintype "bidirectional"))
      (node (ref "U4") (pin "7") (pinfunction "A15_L_7") (pintype "bidirectional"))
    )
    (net (code "169") (name "XMEGA_RD") (class "Default")
      (node (ref "J1") (pin "10") (pinfunction "10_10") (pintype "bidirectional"))
      (node (ref "U1") (pin "34") (pinfunction "PE1(_RD)_34") (pintype "bidirectional"))
      (node (ref "U4") (pin "17") (pinfunction "OE_L_17") (pintype "bidirectional"))
    )
    (net (code "170") (name "XMEGA_WR") (class "Default")
      (node (ref "R50") (pin "1") (pinfunction "1_1") (pintype "bidirectional"))
      (node (ref "U1") (pin "33") (pinfunction "PE0(_WR)_33") (pintype "bidirectional"))
      (node (ref "U4") (pin "16") (pinfunction "RW_L_16") (pintype "bidirectional"))
    )
    (net (code "171") (name "XMEM_ALE{slash}HWB") (class "Default")
      (node (ref "J5") (pin "1") (pinfunction "1_1") (pintype "bidirectional"))
      (node (ref "R9") (pin "2") (pinfunction "2_2") (pintype "bidirectional"))
      (node (ref "U1") (pin "43") (pinfunction "PE2(ALE/_HWB)_43") (pintype "bidirectional"))
      (node (ref "U13") (pin "11") (pinfunction "LE_11") (pintype "bidirectional"))
    )
    (net (code "172") (name "unconnected-(J8-SHIELD-PadCASE_1)") (class "Default")
      (node (ref "J8") (pin "CASE_1") (pinfunction "SHIELD_CASE_1") (pintype "bidirectional"))
    )
    (net (code "173") (name "unconnected-(J8-UID-Pad4)") (class "Default")
      (node (ref "J8") (pin "4") (pinfunction "UID_4") (pintype "bidirectional"))
    )
    (net (code "174") (name "unconnected-(J11-SHIELD-PadCASE_1)") (class "Default")
      (node (ref "J11") (pin "CASE_1") (pinfunction "SHIELD_CASE_1") (pintype "bidirectional"))
    )
    (net (code "175") (name "unconnected-(U3-AREF-Pad42)") (class "Default")
      (node (ref "U3") (pin "42") (pinfunction "AREF_42") (pintype "bidirectional"))
    )
    (net (code "176") (name "unconnected-(U3-PB0(SS{slash}PCINT0)-Pad8)") (class "Default")
      (node (ref "U3") (pin "8") (pinfunction "PB0(SS/PCINT0)_8") (pintype "bidirectional"))
    )
    (net (code "177") (name "unconnected-(U3-PB4(PCINT4{slash}ADC11)-Pad28)") (class "Default")
      (node (ref "U3") (pin "28") (pinfunction "PB4(PCINT4/ADC11)_28") (pintype "bidirectional"))
    )
    (net (code "178") (name "unconnected-(U3-PB5(PCINT5(OC1A{slash}OC4B{slash}ADC12)-Pad29)") (class "Default")
      (node (ref "U3") (pin "29") (pinfunction "PB5(PCINT5(OC1A/OC4B/ADC12)_29") (pintype "bidirectional"))
    )
    (net (code "179") (name "unconnected-(U3-PB6(PCINT6{slash}OC1B{slash}OC4B{slash}ADC13)-Pad30)") (class "Default")
      (node (ref "U3") (pin "30") (pinfunction "PB6(PCINT6/OC1B/OC4B/ADC13)_30") (pintype "bidirectional"))
    )
    (net (code "180") (name "unconnected-(U3-PB7(PCINT7{slash}OC0A{slash}OC1C{slash}RTS)-Pad12)") (class "Default")
      (node (ref "U3") (pin "12") (pinfunction "PB7(PCINT7/OC0A/OC1C/RTS)_12") (pintype "bidirectional"))
    )
    (net (code "181") (name "unconnected-(U3-PC6(OC3A{slash}OC4A)-Pad31)") (class "Default")
      (node (ref "U3") (pin "31") (pinfunction "PC6(OC3A/OC4A)_31") (pintype "bidirectional"))
    )
    (net (code "182") (name "unconnected-(U3-PC7(ICP3{slash}CLK0{slash}OC4A)-Pad32)") (class "Default")
      (node (ref "U3") (pin "32") (pinfunction "PC7(ICP3/CLK0/OC4A)_32") (pintype "bidirectional"))
    )
    (net (code "183") (name "unconnected-(U3-PD4(ICP1{slash}ADC8)-Pad25)") (class "Default")
      (node (ref "U3") (pin "25") (pinfunction "PD4(ICP1/ADC8)_25") (pintype "bidirectional"))
    )
    (net (code "184") (name "unconnected-(U3-PD5(XCK1{slash}CTS)-Pad22)") (class "Default")
      (node (ref "U3") (pin "22") (pinfunction "PD5(XCK1/CTS)_22") (pintype "bidirectional"))
    )
    (net (code "185") (name "unconnected-(U3-PD6(T1{slash}OC4D{slash}ADC9)-Pad26)") (class "Default")
      (node (ref "U3") (pin "26") (pinfunction "PD6(T1/OC4D/ADC9)_26") (pintype "bidirectional"))
    )
    (net (code "186") (name "unconnected-(U3-PD7(T0{slash}OC4D{slash}ADC10)-Pad27)") (class "Default")
      (node (ref "U3") (pin "27") (pinfunction "PD7(T0/OC4D/ADC10)_27") (pintype "bidirectional"))
    )
    (net (code "187") (name "unconnected-(U3-PF0(ADC0)-Pad41)") (class "Default")
      (node (ref "U3") (pin "41") (pinfunction "PF0(ADC0)_41") (pintype "bidirectional"))
    )
    (net (code "188") (name "unconnected-(U3-PF1(ADC1)-Pad40)") (class "Default")
      (node (ref "U3") (pin "40") (pinfunction "PF1(ADC1)_40") (pintype "bidirectional"))
    )
    (net (code "189") (name "unconnected-(U3-PF4(ADC4{slash}TCK)-Pad39)") (class "Default")
      (node (ref "U3") (pin "39") (pinfunction "PF4(ADC4/TCK)_39") (pintype "bidirectional"))
    )
    (net (code "190") (name "unconnected-(U3-PF5(ADC5{slash}TMS)-Pad38)") (class "Default")
      (node (ref "U3") (pin "38") (pinfunction "PF5(ADC5/TMS)_38") (pintype "bidirectional"))
    )
    (net (code "191") (name "unconnected-(U3-PF6(ADC6{slash}TDO)-Pad37)") (class "Default")
      (node (ref "U3") (pin "37") (pinfunction "PF6(ADC6/TDO)_37") (pintype "bidirectional"))
    )
    (net (code "192") (name "unconnected-(U3-PF7(ADC7{slash}TDI)-Pad36)") (class "Default")
      (node (ref "U3") (pin "36") (pinfunction "PF7(ADC7/TDI)_36") (pintype "bidirectional"))
    )
    (net (code "193") (name "unconnected-(U4-BUSY_L-Pad89)") (class "Default")
      (node (ref "U4") (pin "89") (pinfunction "BUSY_L_89") (pintype "bidirectional"))
    )
    (net (code "194") (name "unconnected-(U4-BUSY_R-Pad86)") (class "Default")
      (node (ref "U4") (pin "86") (pinfunction "BUSY_R_86") (pintype "bidirectional"))
    )
    (net (code "195") (name "unconnected-(U4-D8_L-Pad27)") (class "Default")
      (node (ref "U4") (pin "27") (pinfunction "D8_L_27") (pintype "bidirectional"))
    )
    (net (code "196") (name "unconnected-(U4-D8_R-Pad48)") (class "Default")
      (node (ref "U4") (pin "48") (pinfunction "D8_R_48") (pintype "bidirectional"))
    )
    (net (code "197") (name "unconnected-(U4-D9_L-Pad26)") (class "Default")
      (node (ref "U4") (pin "26") (pinfunction "D9_L_26") (pintype "bidirectional"))
    )
    (net (code "198") (name "unconnected-(U4-D9_R-Pad49)") (class "Default")
      (node (ref "U4") (pin "49") (pinfunction "D9_R_49") (pintype "bidirectional"))
    )
    (net (code "199") (name "unconnected-(U4-D10_L-Pad25)") (class "Default")
      (node (ref "U4") (pin "25") (pinfunction "D10_L_25") (pintype "bidirectional"))
    )
    (net (code "200") (name "unconnected-(U4-D10_R-Pad51)") (class "Default")
      (node (ref "U4") (pin "51") (pinfunction "D10_R_51") (pintype "bidirectional"))
    )
    (net (code "201") (name "unconnected-(U4-D11_L-Pad24)") (class "Default")
      (node (ref "U4") (pin "24") (pinfunction "D11_L_24") (pintype "bidirectional"))
    )
    (net (code "202") (name "unconnected-(U4-D11_R-Pad52)") (class "Default")
      (node (ref "U4") (pin "52") (pinfunction "D11_R_52") (pintype "bidirectional"))
    )
    (net (code "203") (name "unconnected-(U4-D12_L-Pad23)") (class "Default")
      (node (ref "U4") (pin "23") (pinfunction "D12_L_23") (pintype "bidirectional"))
    )
    (net (code "204") (name "unconnected-(U4-D12_R-Pad53)") (class "Default")
      (node (ref "U4") (pin "53") (pinfunction "D12_R_53") (pintype "bidirectional"))
    )
    (net (code "205") (name "unconnected-(U4-D13_L-Pad22)") (class "Default")
      (node (ref "U4") (pin "22") (pinfunction "D13_L_22") (pintype "bidirectional"))
    )
    (net (code "206") (name "unconnected-(U4-D13_R-Pad54)") (class "Default")
      (node (ref "U4") (pin "54") (pinfunction "D13_R_54") (pintype "bidirectional"))
    )
    (net (code "207") (name "unconnected-(U4-D14_L-Pad21)") (class "Default")
      (node (ref "U4") (pin "21") (pinfunction "D14_L_21") (pintype "bidirectional"))
    )
    (net (code "208") (name "unconnected-(U4-D14_R-Pad55)") (class "Default")
      (node (ref "U4") (pin "55") (pinfunction "D14_R_55") (pintype "bidirectional"))
    )
    (net (code "209") (name "unconnected-(U4-D15_L-Pad20)") (class "Default")
      (node (ref "U4") (pin "20") (pinfunction "D15_L_20") (pintype "bidirectional"))
    )
    (net (code "210") (name "unconnected-(U4-D15_R-Pad56)") (class "Default")
      (node (ref "U4") (pin "56") (pinfunction "D15_R_56") (pintype "bidirectional"))
    )
    (net (code "211") (name "unconnected-(U4-INT_L-Pad90)") (class "Default")
      (node (ref "U4") (pin "90") (pinfunction "INT_L_90") (pintype "bidirectional"))
    )
    (net (code "212") (name "unconnected-(U4-INT_R-Pad85)") (class "Default")
      (node (ref "U4") (pin "85") (pinfunction "INT_R_85") (pintype "bidirectional"))
    )
    (net (code "213") (name "unconnected-(U4-NC-Pad8)") (class "Default")
      (node (ref "U4") (pin "8") (pinfunction "NC_8") (pintype "no_connect"))
    )
    (net (code "214") (name "unconnected-(U4-NC-Pad9)") (class "Default")
      (node (ref "U4") (pin "9") (pinfunction "NC_9") (pintype "no_connect"))
    )
    (net (code "215") (name "unconnected-(U4-NC-Pad50)") (class "Default")
      (node (ref "U4") (pin "50") (pinfunction "NC_50") (pintype "no_connect"))
    )
    (net (code "216") (name "unconnected-(U4-NC-Pad67)") (class "Default")
      (node (ref "U4") (pin "67") (pinfunction "NC_67") (pintype "no_connect"))
    )
    (net (code "217") (name "unconnected-(U4-NC-Pad68)") (class "Default")
      (node (ref "U4") (pin "68") (pinfunction "NC_68") (pintype "no_connect"))
    )
    (net (code "218") (name "unconnected-(U4-NC-Pad91)") (class "Default")
      (node (ref "U4") (pin "91") (pinfunction "NC_91") (pintype "no_connect"))
    )
    (net (code "219") (name "unconnected-(U5-IO_0_34-PadB6)") (class "Default")
      (node (ref "U5") (pin "B6") (pinfunction "IO_0_34_B6") (pintype "bidirectional"))
    )
    (net (code "220") (name "unconnected-(U5-IO_L1N_T0_34-PadC3)") (class "Default")
      (node (ref "U5") (pin "C3") (pinfunction "IO_L1N_T0_34_C3") (pintype "bidirectional"))
    )
    (net (code "221") (name "unconnected-(U5-IO_L1P_T0_34-PadD3)") (class "Default")
      (node (ref "U5") (pin "D3") (pinfunction "IO_L1P_T0_34_D3") (pintype "bidirectional"))
    )
    (net (code "222") (name "unconnected-(U5-IO_L3P_T0_DQS_34-PadB3)") (class "Default")
      (node (ref "U5") (pin "B3") (pinfunction "IO_L3P_T0_DQS_34_B3") (pintype "bidirectional"))
    )
    (net (code "223") (name "unconnected-(U5-IO_L3P_T0_DQS_PUDC_B_14-PadB10)") (class "Default")
      (node (ref "U5") (pin "B10") (pinfunction "IO_L3P_T0_DQS_PUDC_B_14_B10") (pintype "bidirectional"))
    )
    (net (code "224") (name "unconnected-(U5-IO_L4P_T0_34-PadB5)") (class "Default")
      (node (ref "U5") (pin "B5") (pinfunction "IO_L4P_T0_34_B5") (pintype "bidirectional"))
    )
    (net (code "225") (name "unconnected-(U5-IO_L5N_T0_34-PadB1)") (class "Default")
      (node (ref "U5") (pin "B1") (pinfunction "IO_L5N_T0_34_B1") (pintype "bidirectional"))
    )
    (net (code "226") (name "unconnected-(U5-IO_L5P_T0_34-PadB2)") (class "Default")
      (node (ref "U5") (pin "B2") (pinfunction "IO_L5P_T0_34_B2") (pintype "bidirectional"))
    )
    (net (code "227") (name "unconnected-(U5-IO_L6N_T0_D08_VREF_14-PadC12)") (class "Default")
      (node (ref "U5") (pin "C12") (pinfunction "IO_L6N_T0_D08_VREF_14_C12") (pintype "bidirectional"))
    )
    (net (code "228") (name "unconnected-(U5-IO_L6N_T0_VREF_34-PadC4)") (class "Default")
      (node (ref "U5") (pin "C4") (pinfunction "IO_L6N_T0_VREF_34_C4") (pintype "bidirectional"))
    )
    (net (code "229") (name "unconnected-(U5-IO_L6P_T0_34-PadC5)") (class "Default")
      (node (ref "U5") (pin "C5") (pinfunction "IO_L6P_T0_34_C5") (pintype "bidirectional"))
    )
    (net (code "230") (name "unconnected-(U5-IO_L7N_T1_34-PadD4)") (class "Default")
      (node (ref "U5") (pin "D4") (pinfunction "IO_L7N_T1_34_D4") (pintype "bidirectional"))
    )
    (net (code "231") (name "unconnected-(U5-IO_L7P_T1_34-PadE4)") (class "Default")
      (node (ref "U5") (pin "E4") (pinfunction "IO_L7P_T1_34_E4") (pintype "bidirectional"))
    )
    (net (code "232") (name "unconnected-(U5-IO_L8N_T1_34-PadF2)") (class "Default")
      (node (ref "U5") (pin "F2") (pinfunction "IO_L8N_T1_34_F2") (pintype "bidirectional"))
    )
    (net (code "233") (name "unconnected-(U5-IO_L8N_T1_D12_14-PadD13)") (class "Default")
      (node (ref "U5") (pin "D13") (pinfunction "IO_L8N_T1_D12_14_D13") (pintype "bidirectional"))
    )
    (net (code "234") (name "unconnected-(U5-IO_L8P_T1_34-PadF3)") (class "Default")
      (node (ref "U5") (pin "F3") (pinfunction "IO_L8P_T1_34_F3") (pintype "bidirectional"))
    )
    (net (code "235") (name "unconnected-(U5-IO_L9N_T1_DQS_34-PadF1)") (class "Default")
      (node (ref "U5") (pin "F1") (pinfunction "IO_L9N_T1_DQS_34_F1") (pintype "bidirectional"))
    )
    (net (code "236") (name "unconnected-(U5-IO_L9P_T1_DQS_34-PadG1)") (class "Default")
      (node (ref "U5") (pin "G1") (pinfunction "IO_L9P_T1_DQS_34_G1") (pintype "bidirectional"))
    )
    (net (code "237") (name "unconnected-(U5-IO_L10N_T1_34-PadD2)") (class "Default")
      (node (ref "U5") (pin "D2") (pinfunction "IO_L10N_T1_34_D2") (pintype "bidirectional"))
    )
    (net (code "238") (name "unconnected-(U5-IO_L10P_T1_34-PadE2)") (class "Default")
      (node (ref "U5") (pin "E2") (pinfunction "IO_L10P_T1_34_E2") (pintype "bidirectional"))
    )
    (net (code "239") (name "unconnected-(U5-IO_L11N_T1_SRCC_14-PadC14)") (class "Default")
      (node (ref "U5") (pin "C14") (pinfunction "IO_L11N_T1_SRCC_14_C14") (pintype "bidirectional"))
    )
    (net (code "240") (name "unconnected-(U5-IO_L11N_T1_SRCC_34-PadC1)") (class "Default")
      (node (ref "U5") (pin "C1") (pinfunction "IO_L11N_T1_SRCC_34_C1") (pintype "bidirectional"))
    )
    (net (code "241") (name "unconnected-(U5-IO_L11P_T1_SRCC_34-PadD1)") (class "Default")
      (node (ref "U5") (pin "D1") (pinfunction "IO_L11P_T1_SRCC_34_D1") (pintype "bidirectional"))
    )
    (net (code "242") (name "unconnected-(U5-IO_L12N_T1_MRCC_34-PadF4)") (class "Default")
      (node (ref "U5") (pin "F4") (pinfunction "IO_L12N_T1_MRCC_34_F4") (pintype "bidirectional"))
    )
    (net (code "243") (name "unconnected-(U5-IO_L12P_T1_MRCC_14-PadG11)") (class "Default")
      (node (ref "U5") (pin "G11") (pinfunction "IO_L12P_T1_MRCC_14_G11") (pintype "bidirectional"))
    )
    (net (code "244") (name "unconnected-(U5-IO_L13N_T2_MRCC_34-PadH3)") (class "Default")
      (node (ref "U5") (pin "H3") (pinfunction "IO_L13N_T2_MRCC_34_H3") (pintype "bidirectional"))
    )
    (net (code "245") (name "unconnected-(U5-IO_L14N_T2_SRCC_14-PadH14)") (class "Default")
      (node (ref "U5") (pin "H14") (pinfunction "IO_L14N_T2_SRCC_14_H14") (pintype "bidirectional"))
    )
    (net (code "246") (name "unconnected-(U5-IO_L14N_T2_SRCC_34-PadH1)") (class "Default")
      (node (ref "U5") (pin "H1") (pinfunction "IO_L14N_T2_SRCC_34_H1") (pintype "bidirectional"))
    )
    (net (code "247") (name "unconnected-(U5-IO_L14P_T2_SRCC_34-PadH2)") (class "Default")
      (node (ref "U5") (pin "H2") (pinfunction "IO_L14P_T2_SRCC_34_H2") (pintype "bidirectional"))
    )
    (net (code "248") (name "unconnected-(U5-IO_L15N_T2_DQS_34-PadJ1)") (class "Default")
      (node (ref "U5") (pin "J1") (pinfunction "IO_L15N_T2_DQS_34_J1") (pintype "bidirectional"))
    )
    (net (code "249") (name "unconnected-(U5-IO_L16N_T2_34-PadK3)") (class "Default")
      (node (ref "U5") (pin "K3") (pinfunction "IO_L16N_T2_34_K3") (pintype "bidirectional"))
    )
    (net (code "250") (name "unconnected-(U5-IO_L16P_T2_34-PadK4)") (class "Default")
      (node (ref "U5") (pin "K4") (pinfunction "IO_L16P_T2_34_K4") (pintype "bidirectional"))
    )
    (net (code "251") (name "unconnected-(U5-IO_L17P_T2_34-PadJ4)") (class "Default")
      (node (ref "U5") (pin "J4") (pinfunction "IO_L17P_T2_34_J4") (pintype "bidirectional"))
    )
    (net (code "252") (name "unconnected-(U5-IO_L19N_T3_VREF_34-PadM2)") (class "Default")
      (node (ref "U5") (pin "M2") (pinfunction "IO_L19N_T3_VREF_34_M2") (pintype "bidirectional"))
    )
    (net (code "253") (name "unconnected-(U5-IO_L19P_T3_34-PadM3)") (class "Default")
      (node (ref "U5") (pin "M3") (pinfunction "IO_L19P_T3_34_M3") (pintype "bidirectional"))
    )
    (net (code "254") (name "unconnected-(U5-IO_L23N_T3_34-PadM4)") (class "Default")
      (node (ref "U5") (pin "M4") (pinfunction "IO_L23N_T3_34_M4") (pintype "bidirectional"))
    )
    (net (code "255") (name "unconnected-(U7-ALERT#-Pad7)") (class "Default")
      (node (ref "U7") (pin "7") (pinfunction "ALERT#_7") (pintype "bidirectional"))
    )
    (net (code "256") (name "unconnected-(U8-ALERT#-Pad7)") (class "Default")
      (node (ref "U8") (pin "7") (pinfunction "ALERT#_7") (pintype "bidirectional"))
    )
    (net (code "257") (name "unconnected-(U9-ALERT#-Pad7)") (class "Default")
      (node (ref "U9") (pin "7") (pinfunction "ALERT#_7") (pintype "bidirectional"))
    )
    (net (code "258") (name "unconnected-(U10-ALERT#-Pad7)") (class "Default")
      (node (ref "U10") (pin "7") (pinfunction "ALERT#_7") (pintype "bidirectional"))
    )
    (net (code "259") (name "unconnected-(U11-RUN2-Pad7)") (class "Default")
      (node (ref "U11") (pin "7") (pinfunction "RUN2_7") (pintype "bidirectional"))
    )
    (net (code "260") (name "unconnected-(U11-SW2-Pad6)") (class "Default")
      (node (ref "U11") (pin "6") (pinfunction "SW2_6") (pintype "bidirectional"))
    )
    (net (code "261") (name "unconnected-(U11-VFB2-Pad8)") (class "Default")
      (node (ref "U11") (pin "8") (pinfunction "VFB2_8") (pintype "bidirectional"))
    )
  )
)
